# full_computer.net
KiCad netlist of a schematic drawn in EAGLE
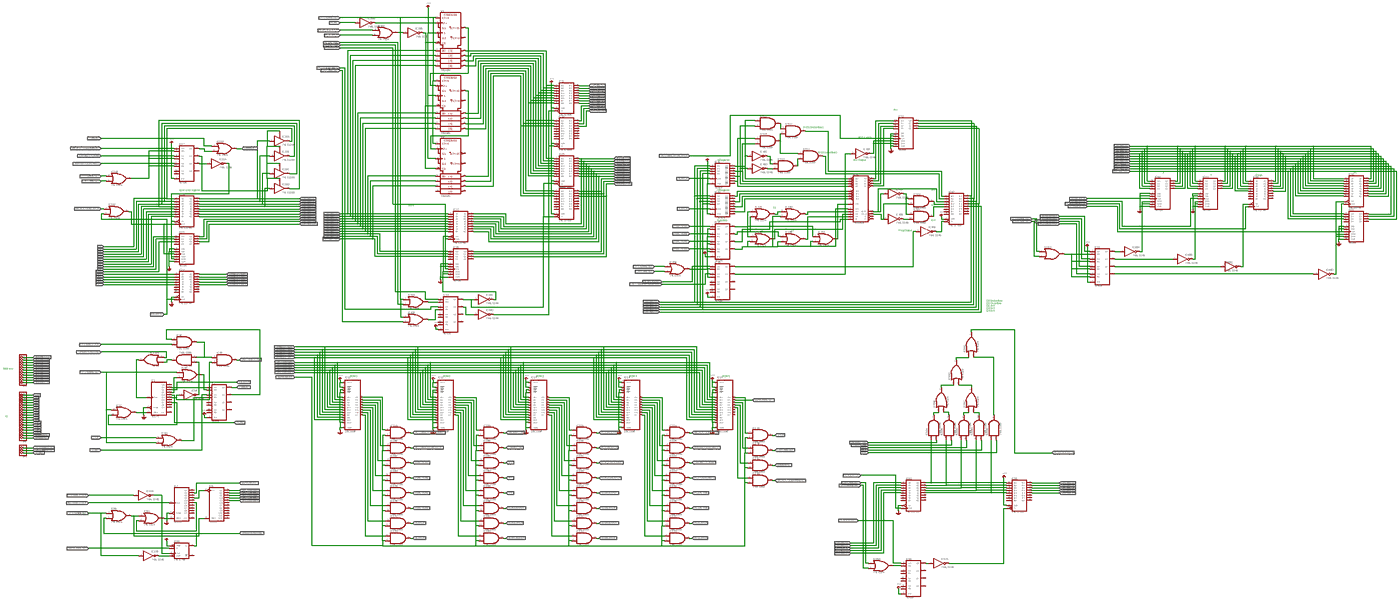
[diagram p0: schematic, sheet 1, overview]
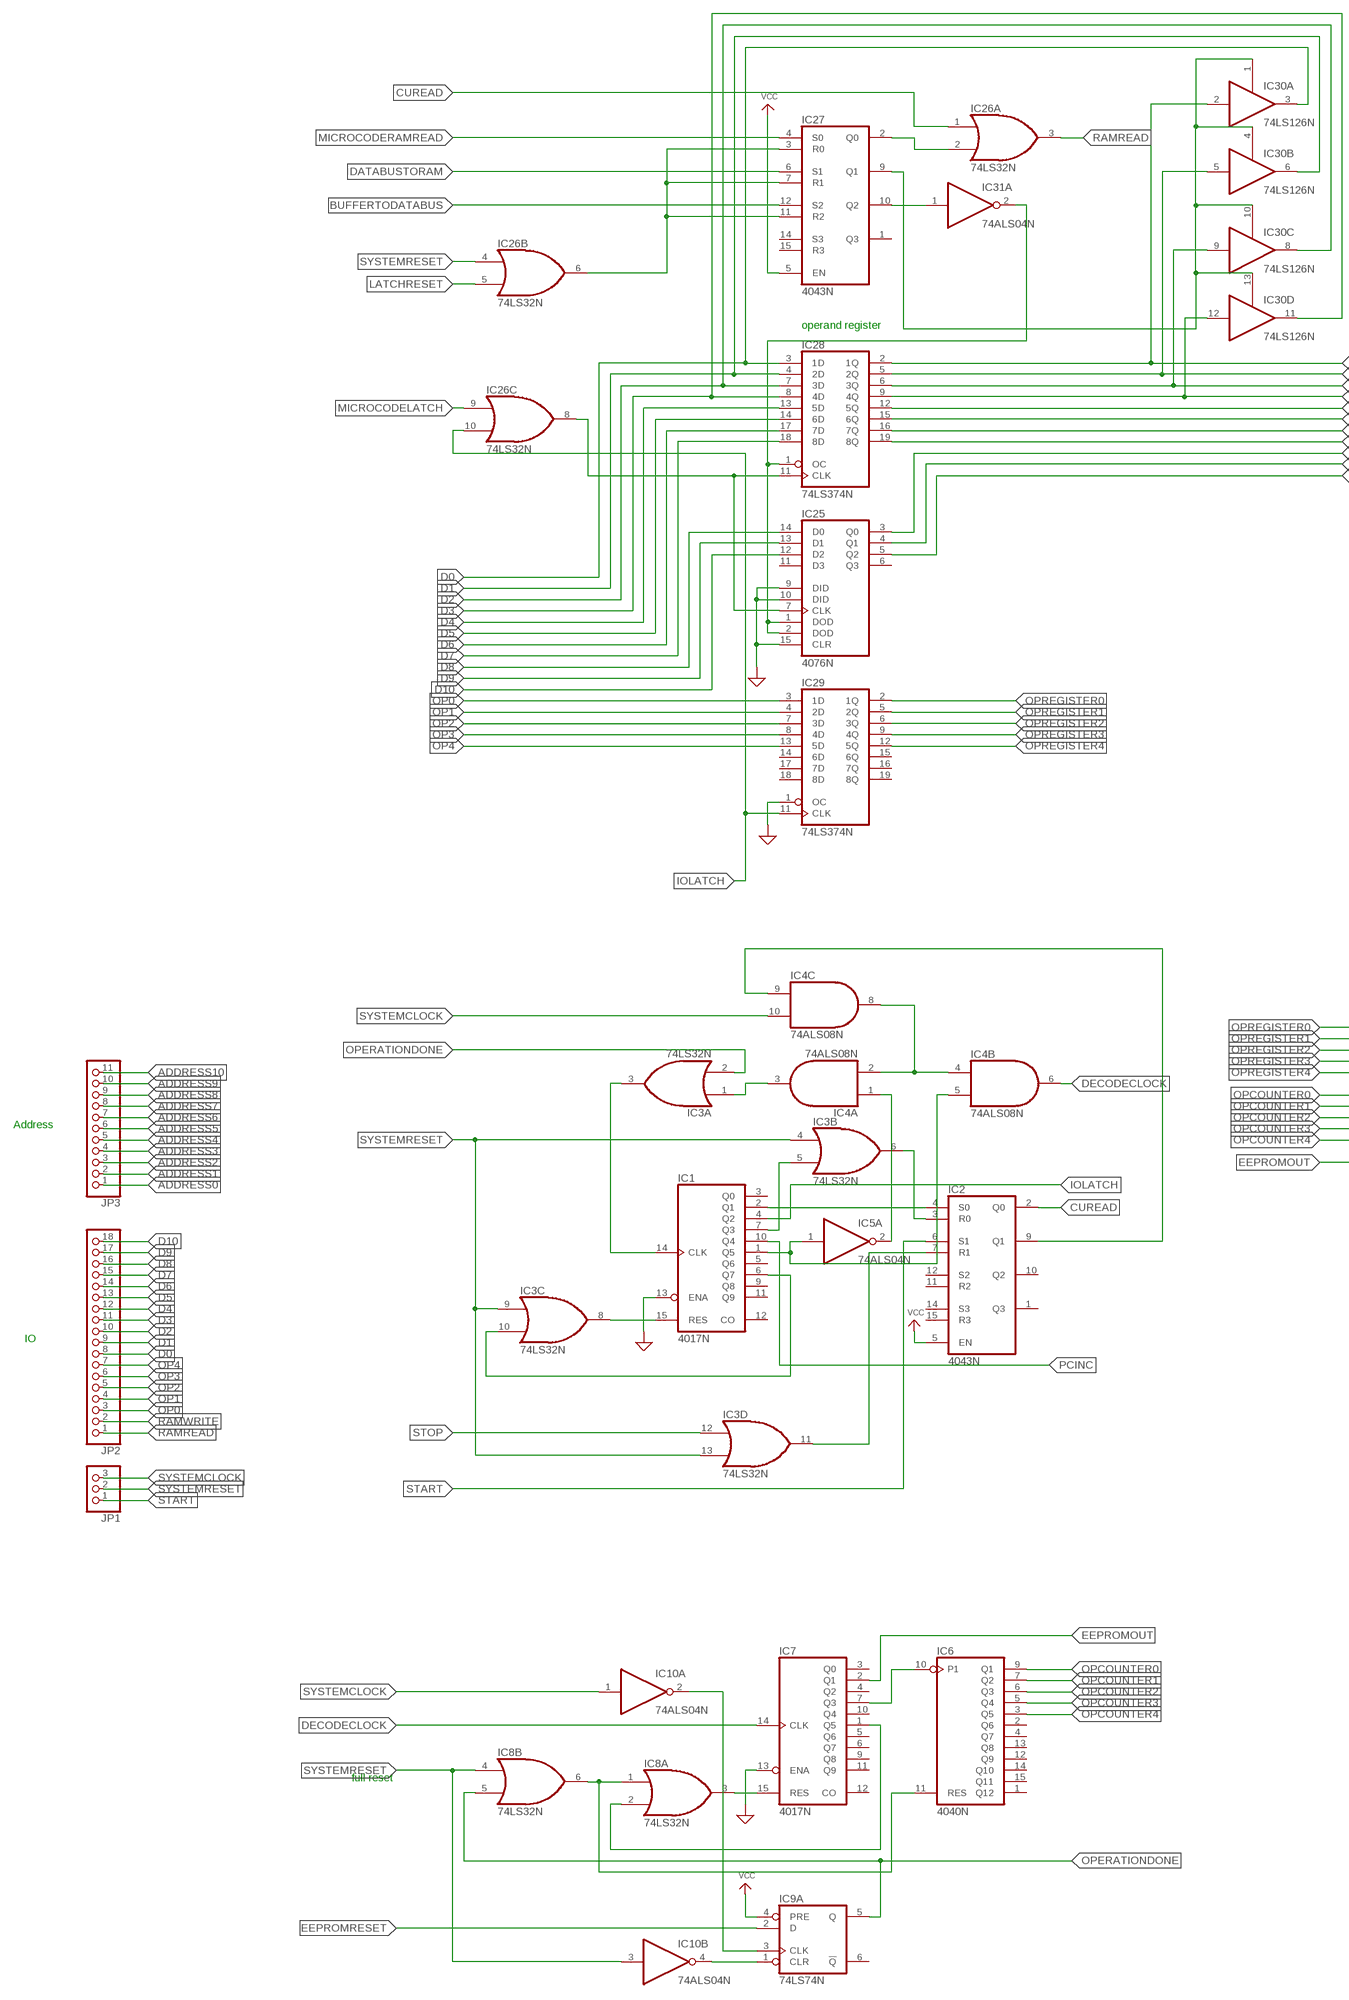
[diagram p1: schematic, sheet 1, part 1 of 6]
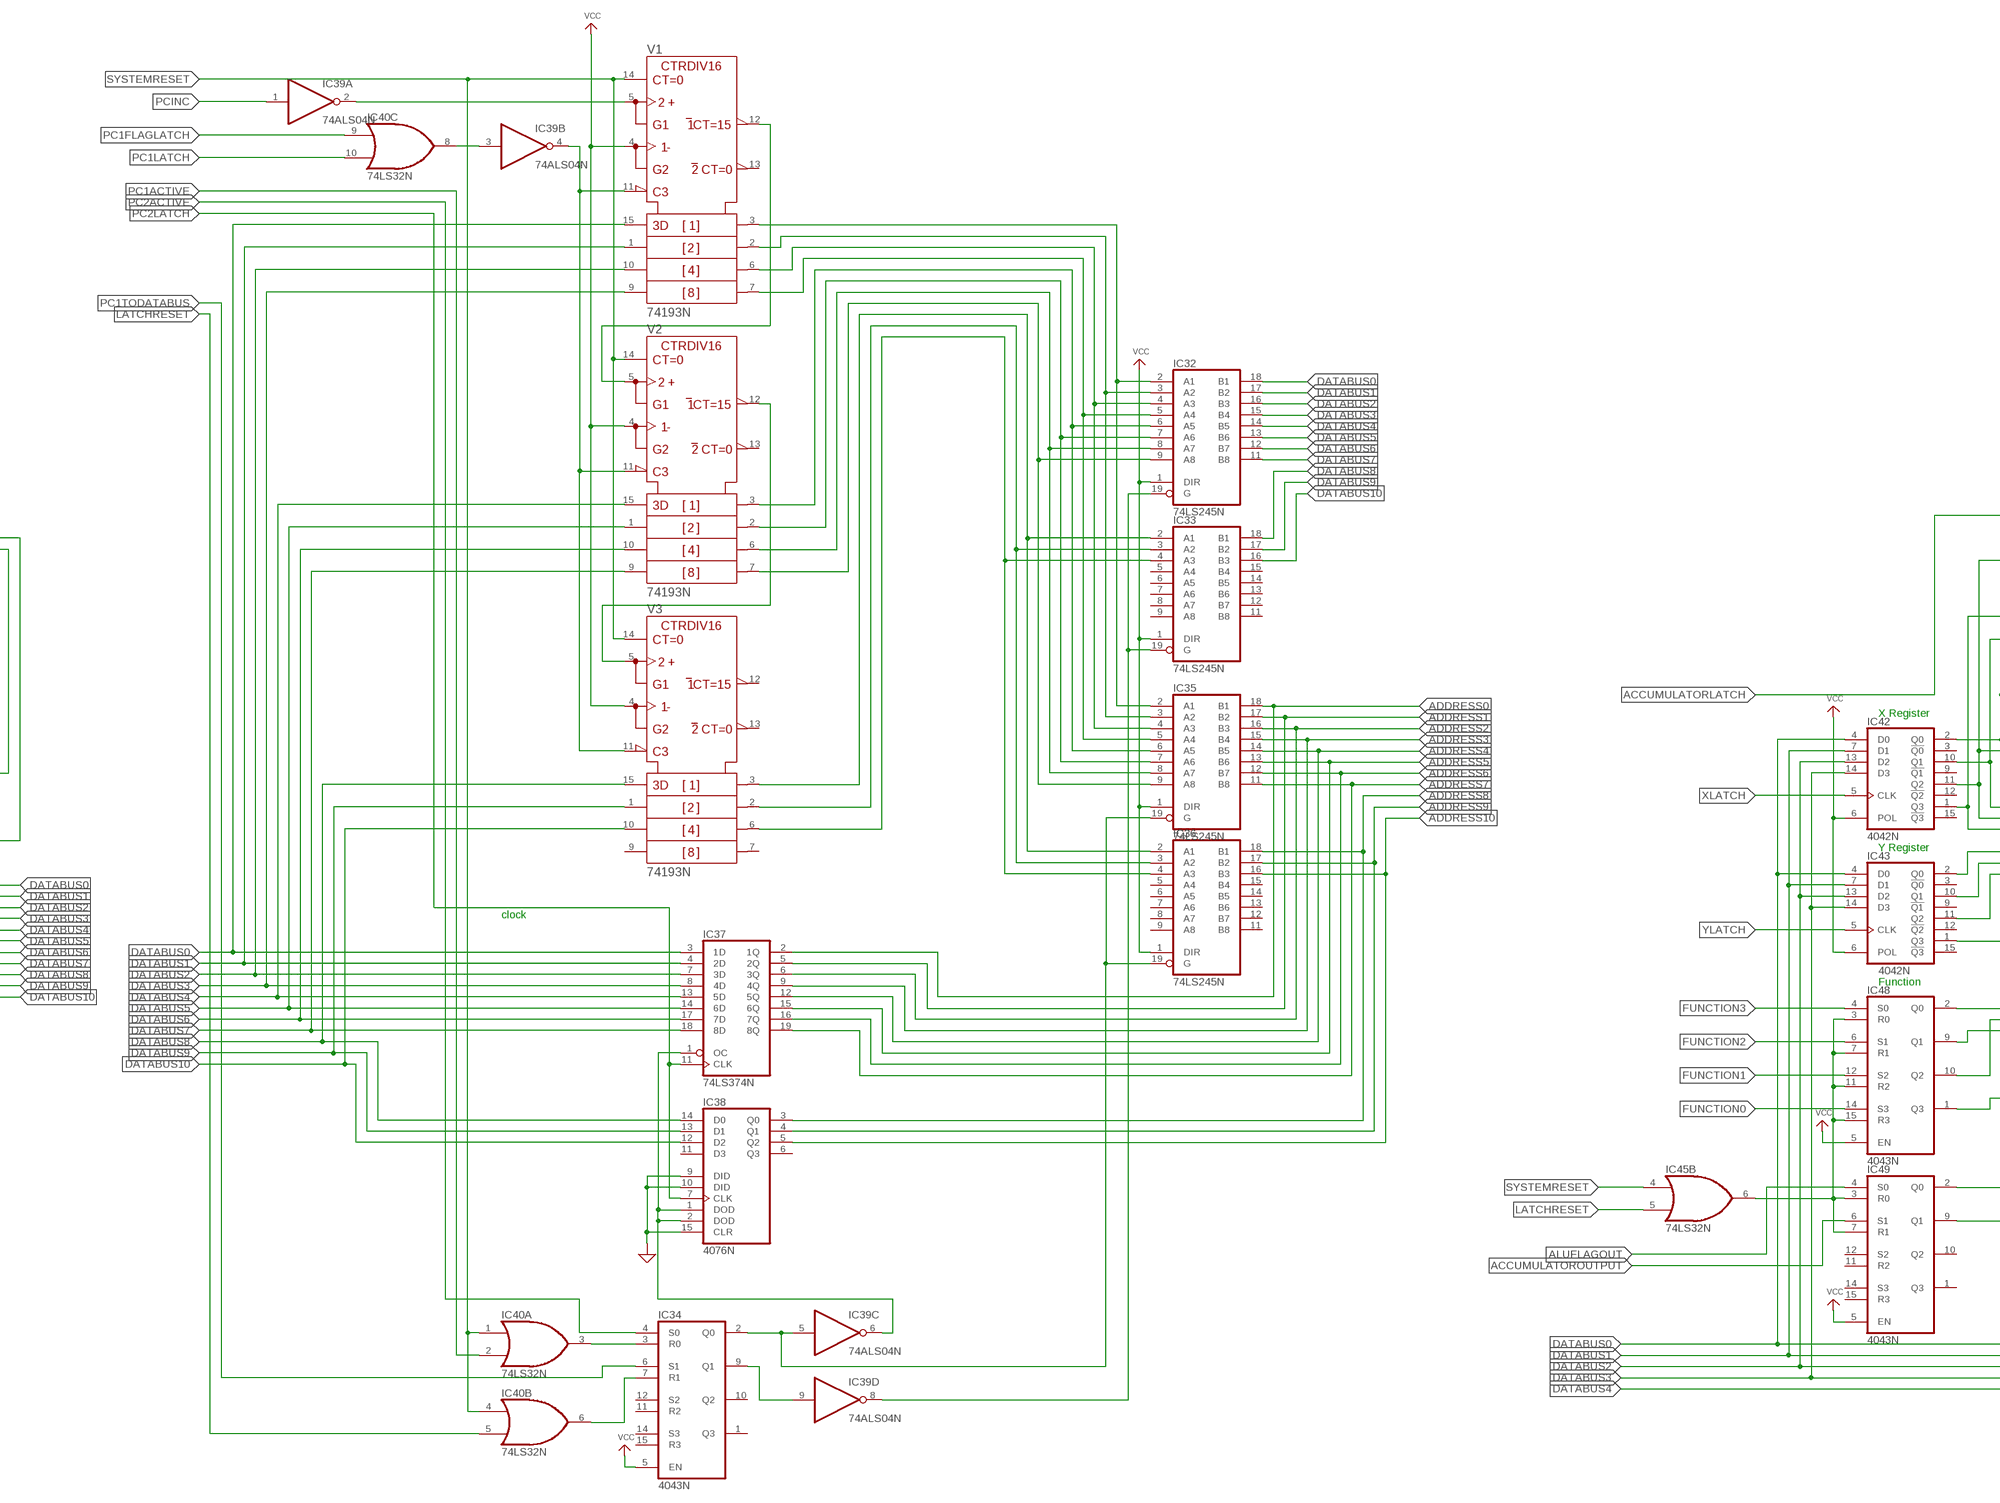
[diagram p2: schematic, sheet 1, part 2 of 6]
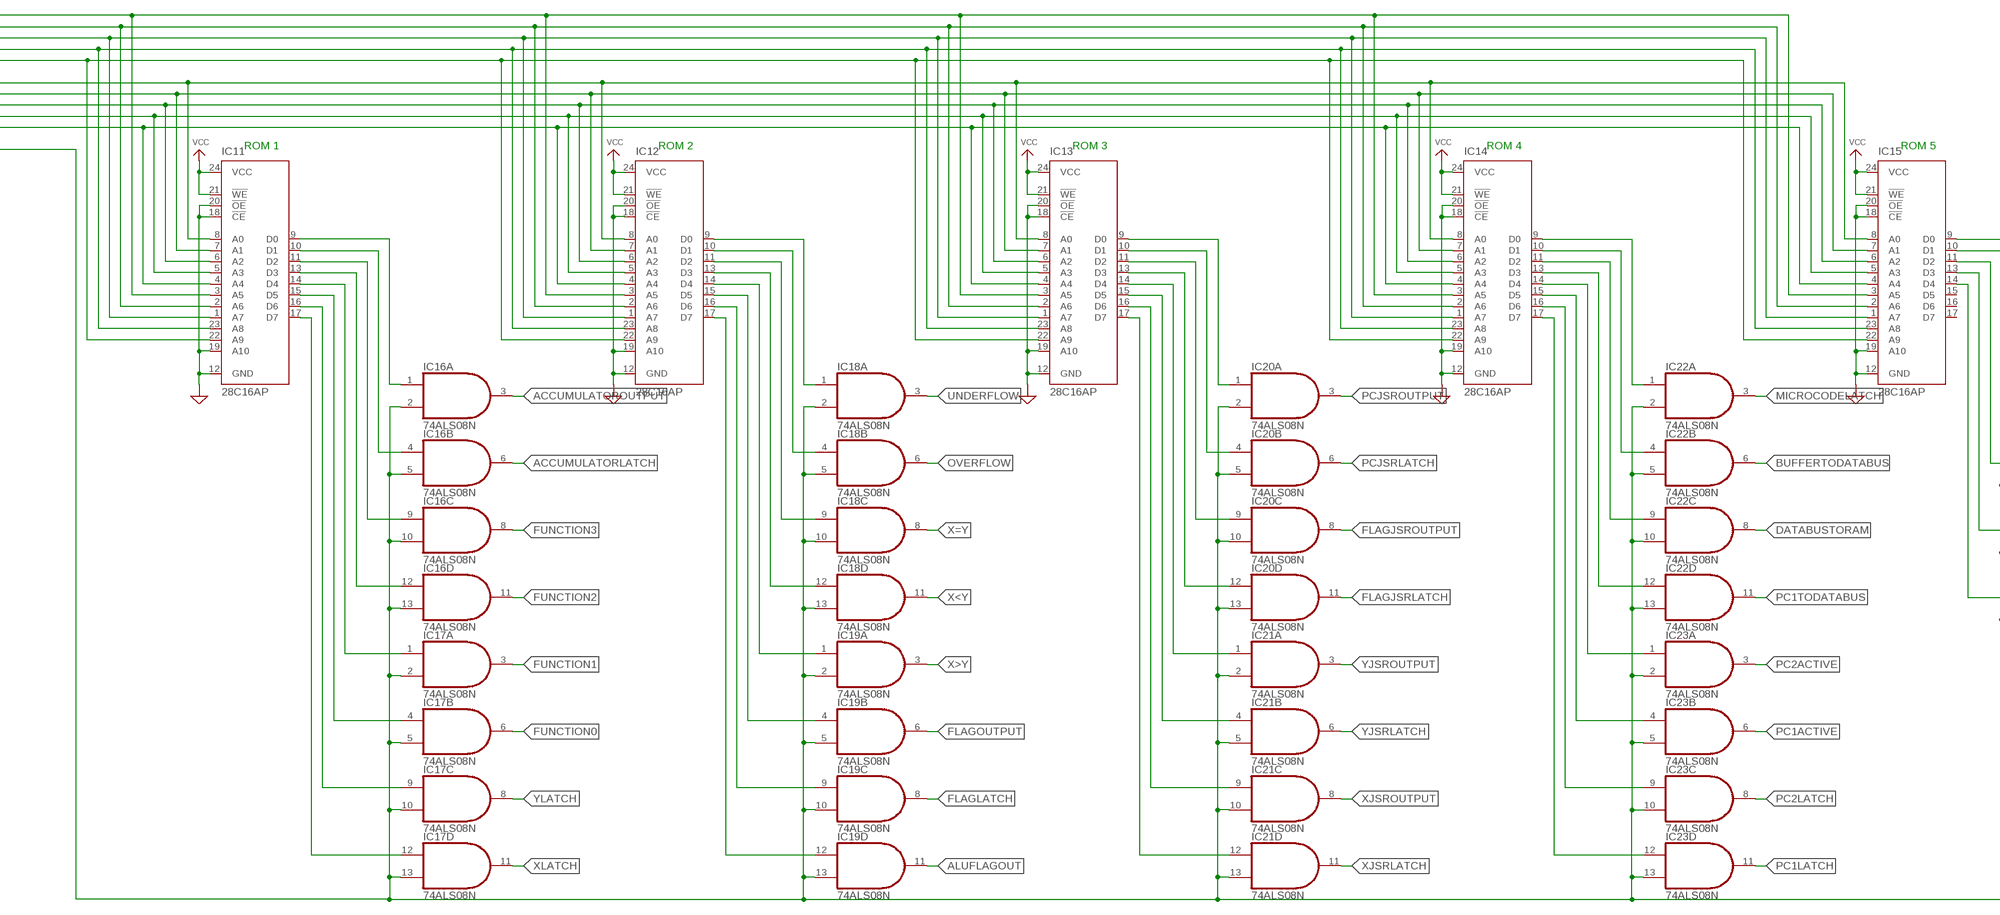
[diagram p3: schematic, sheet 1, part 3 of 6]
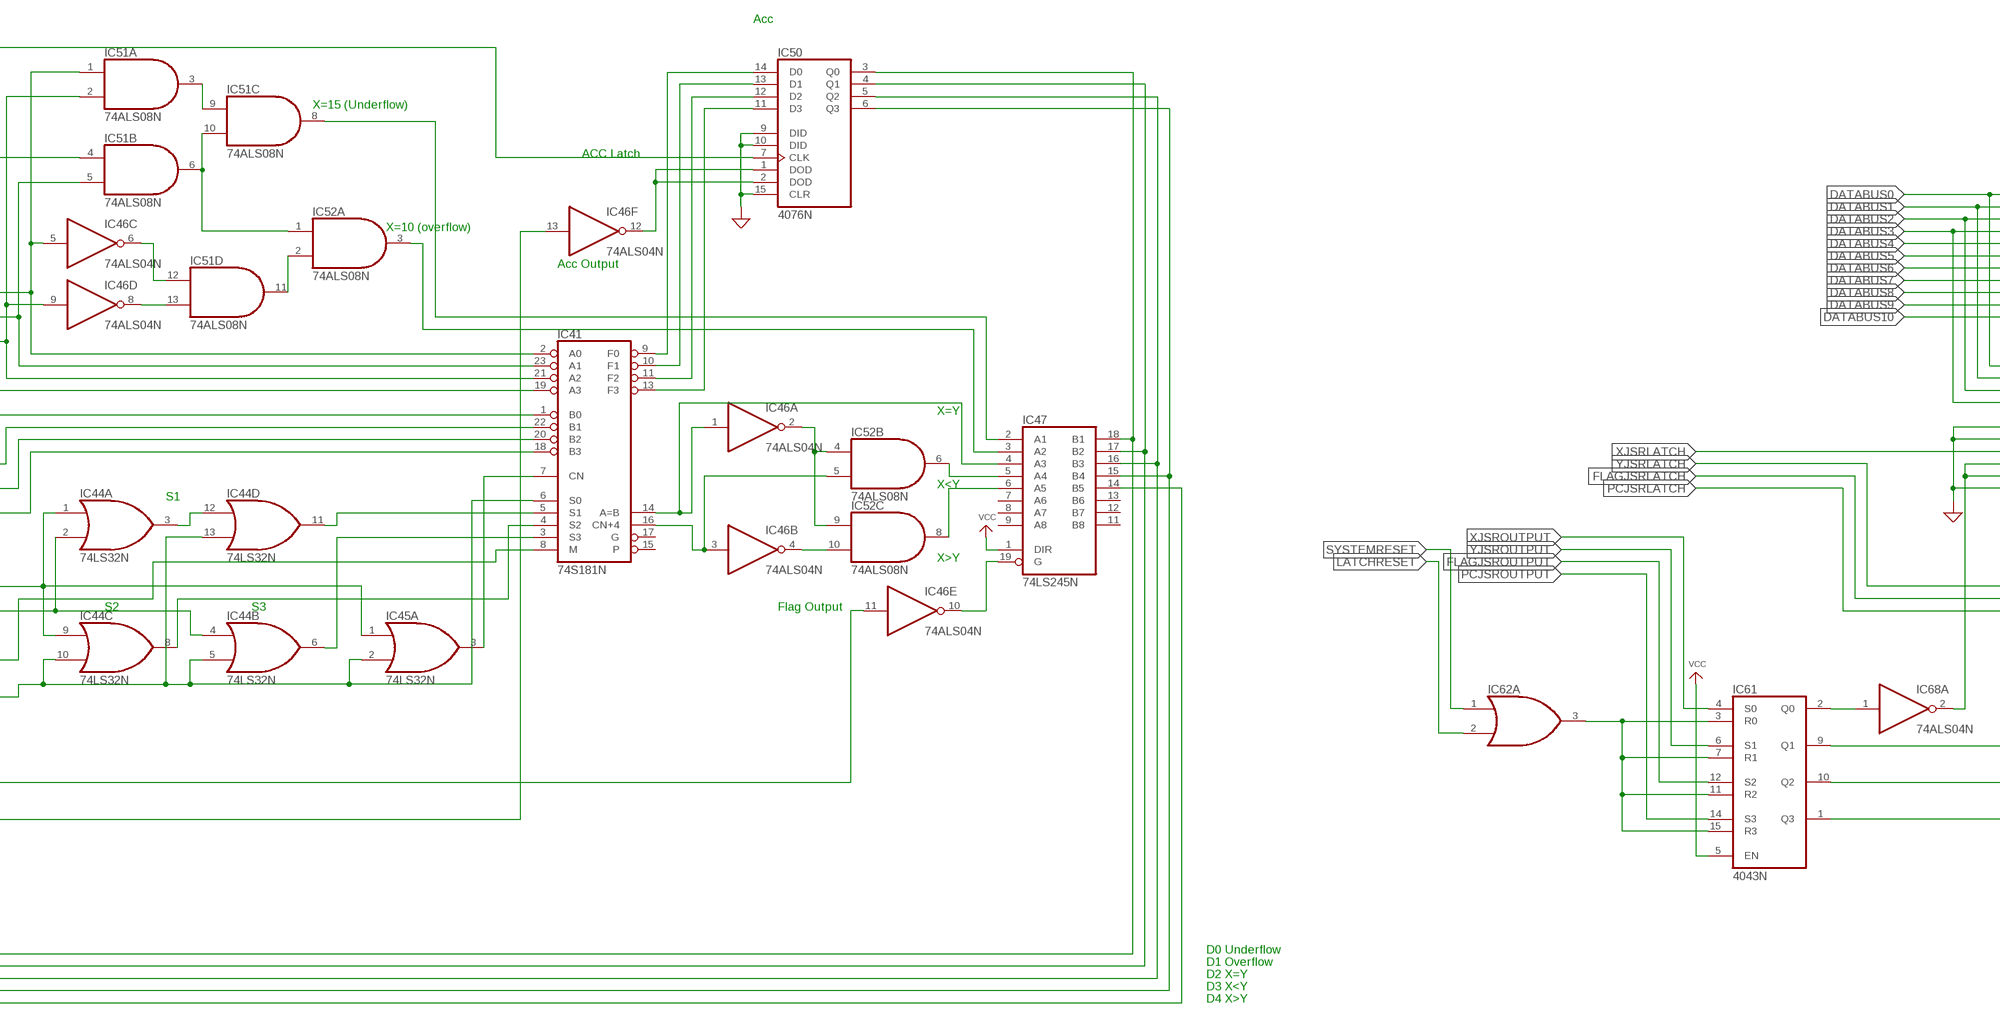
[diagram p4: schematic, sheet 1, part 4 of 6]
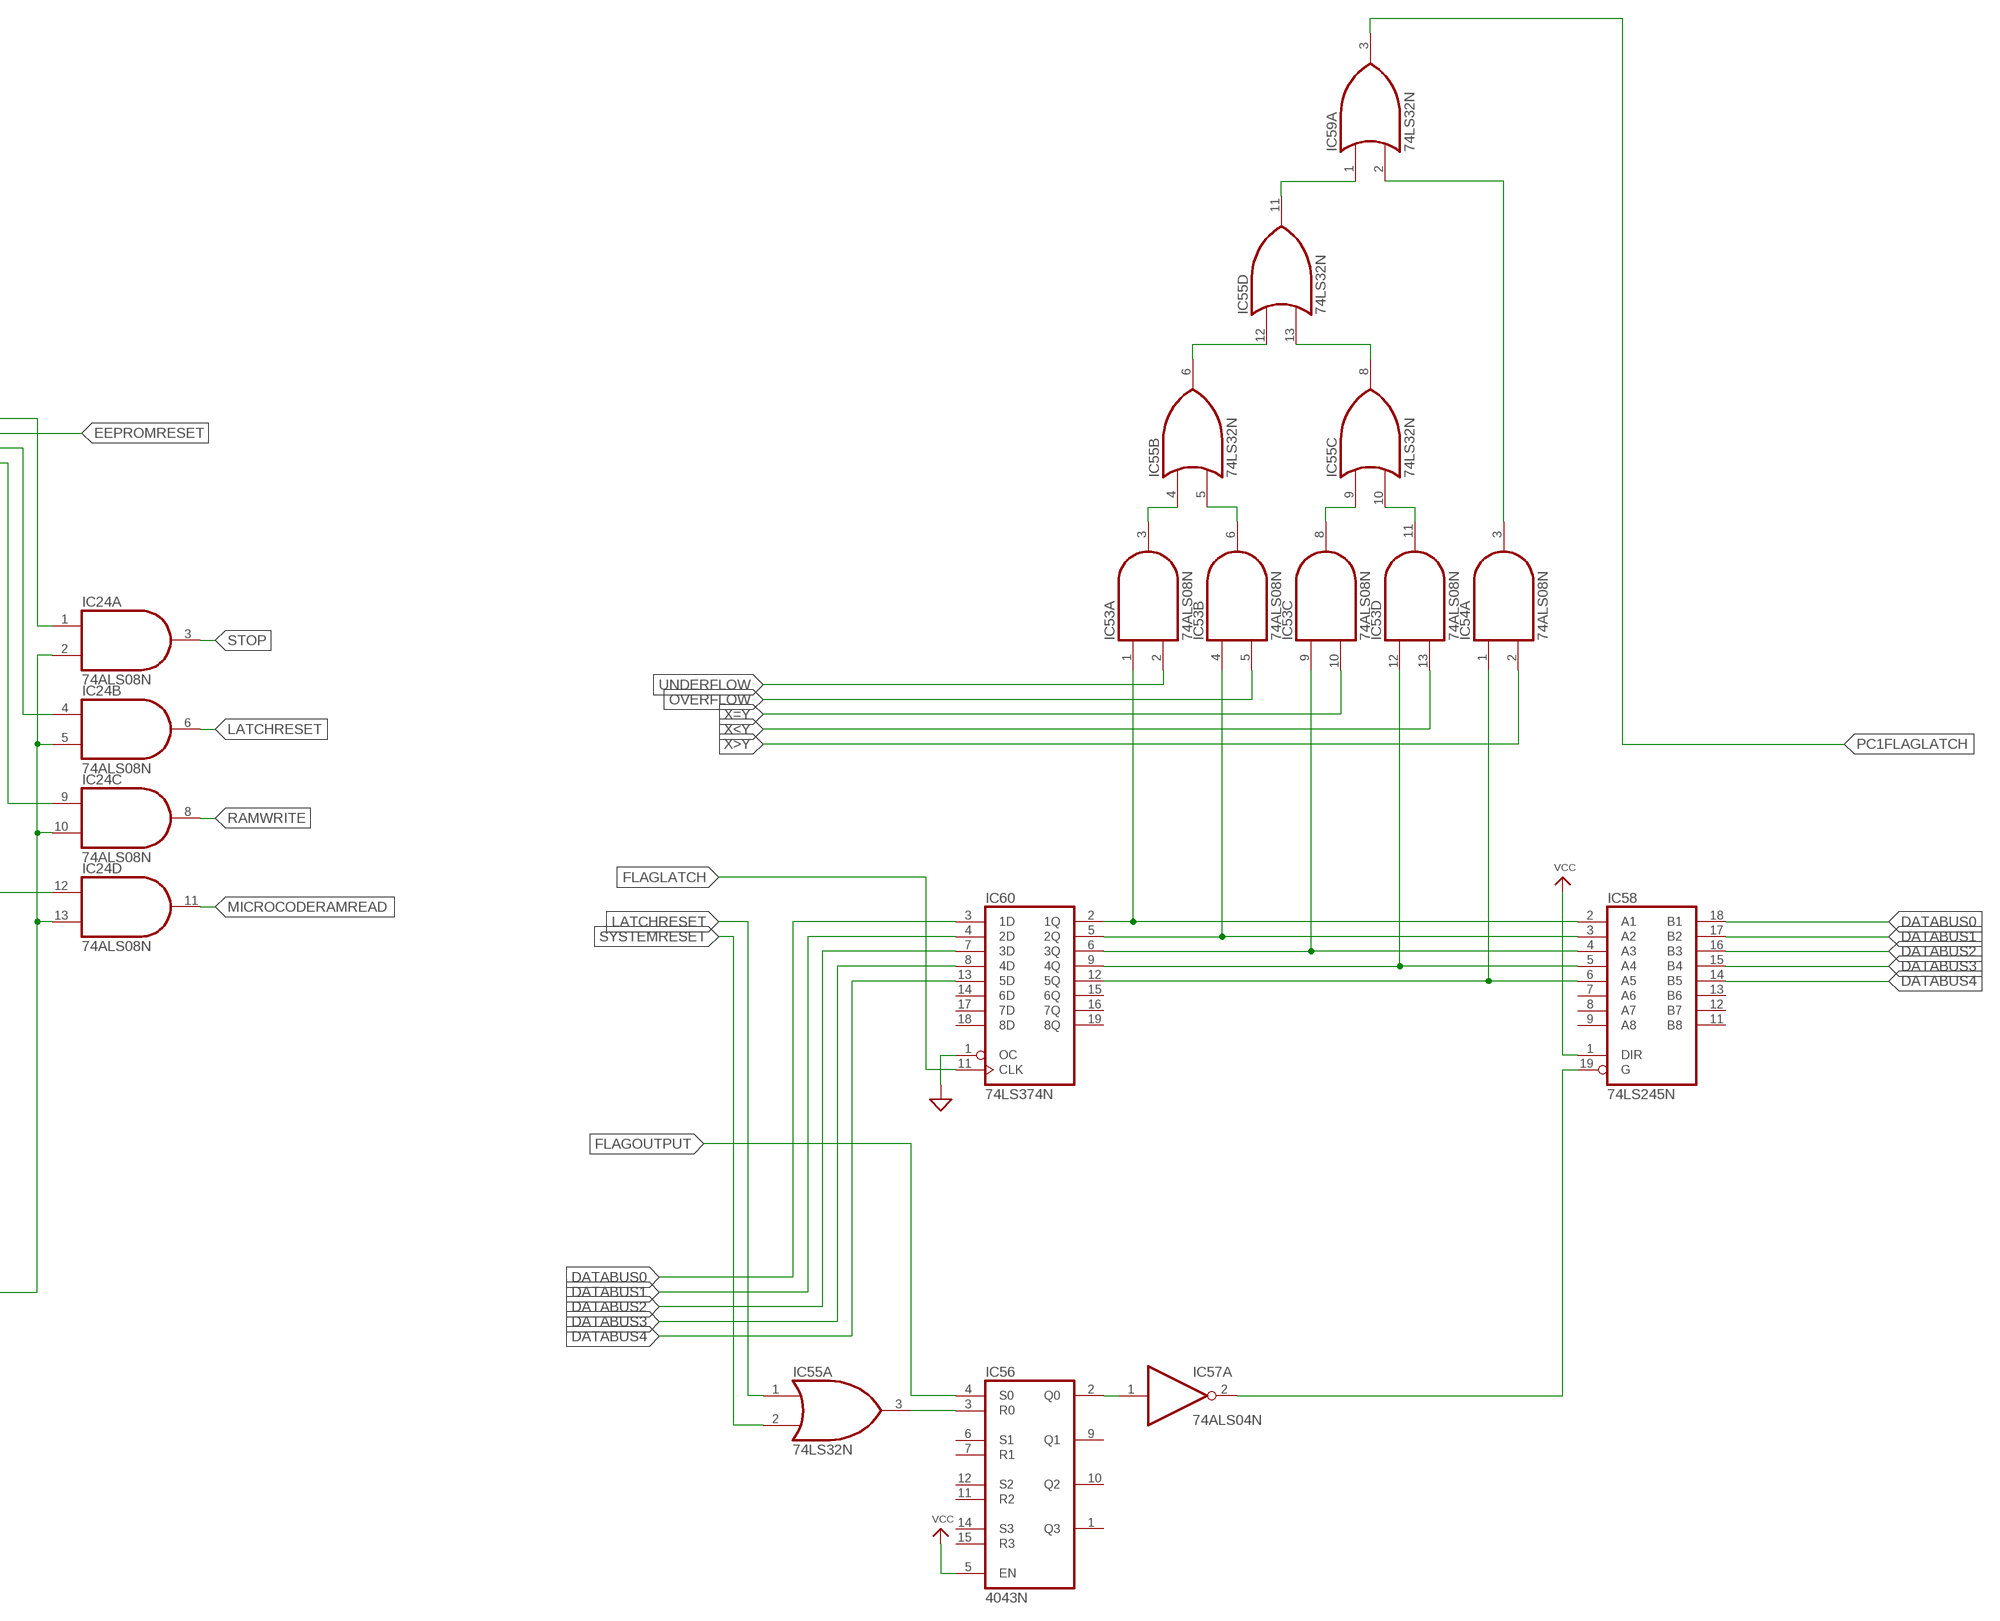
[diagram p5: schematic, sheet 1, part 5 of 6]
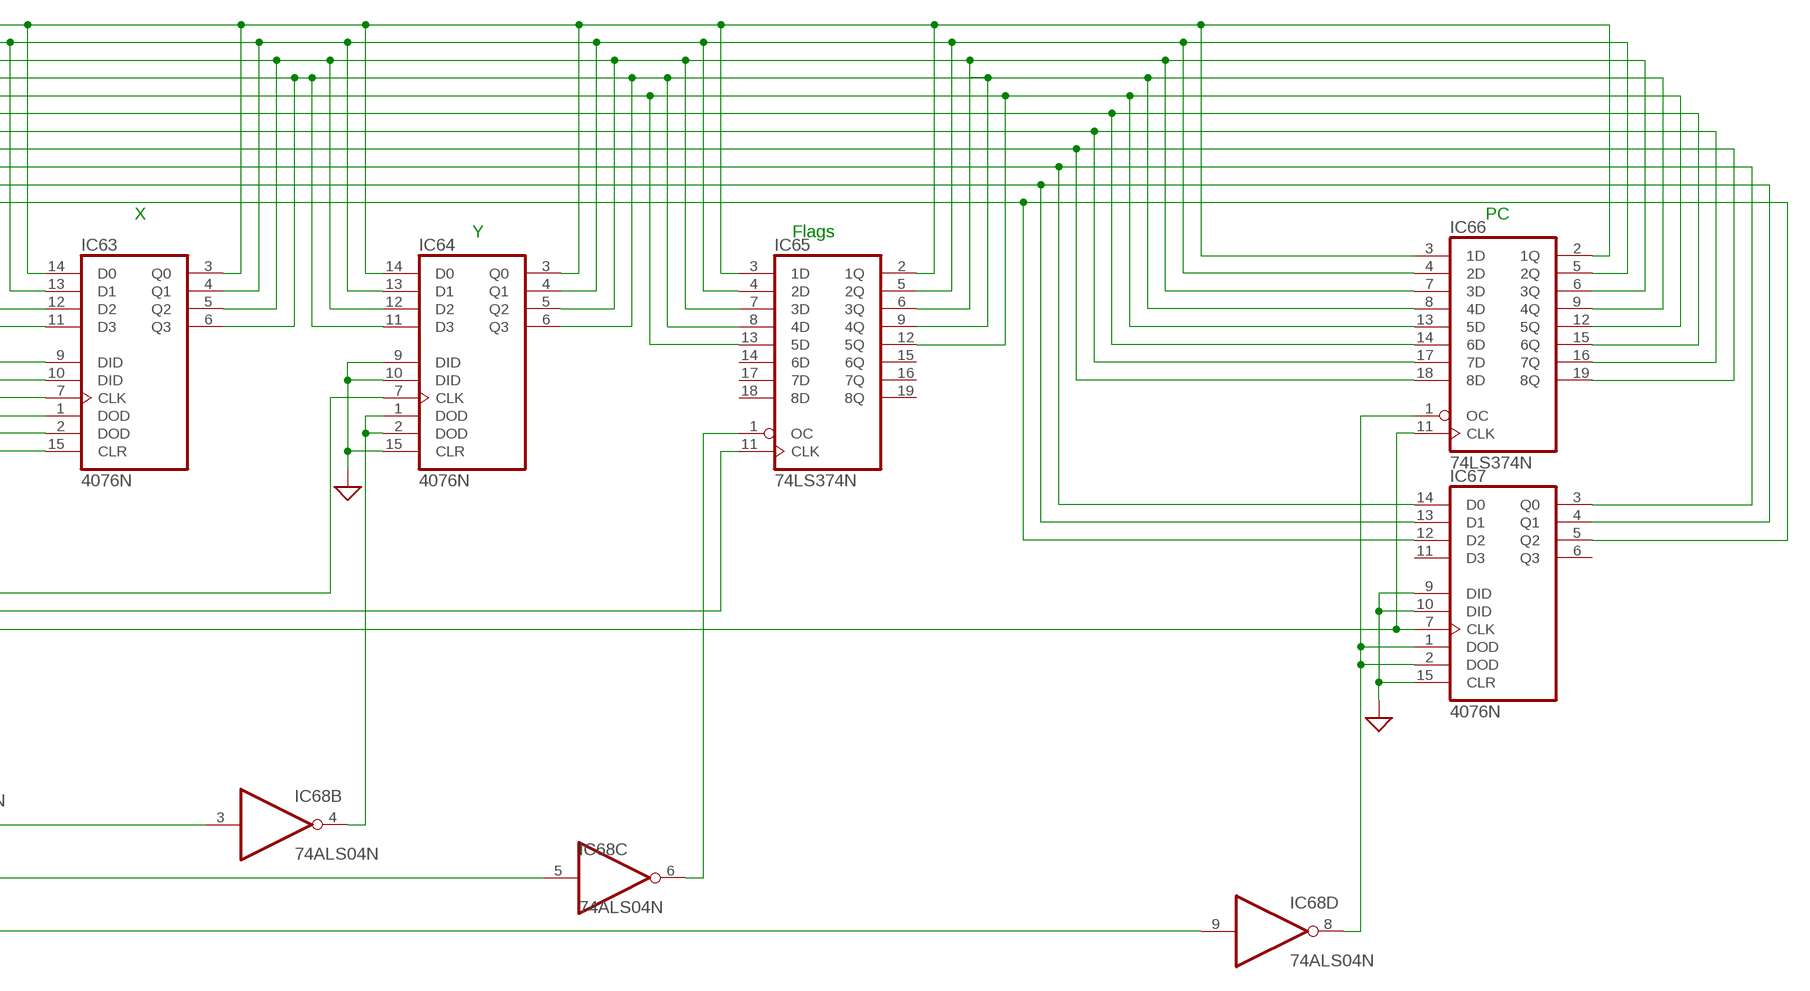
[diagram p6: schematic, sheet 1, part 6 of 6]

(export (version "E")
  (design (tool "Eeschema 10.0.6"))
  (components
    (comp (ref "IC1")
      (value "4017N")
      (footprint "eagle-import:DIL16")
      (libsource (lib "eagle-import") (part "4017N"))
    )
    (comp (ref "IC2")
      (value "4043N")
      (footprint "eagle-import:DIL16")
      (libsource (lib "eagle-import") (part "4043N"))
    )
    (comp (ref "IC3")
      (value "74LS32N")
      (footprint "eagle-import:DIL14")
      (libsource (lib "eagle-import") (part "7432NLS"))
    )
    (comp (ref "IC4")
      (value "74ALS08N")
      (footprint "eagle-import:DIL14")
      (libsource (lib "eagle-import") (part "7408NALS"))
    )
    (comp (ref "IC5")
      (value "74ALS04N")
      (footprint "eagle-import:DIL14")
      (libsource (lib "eagle-import") (part "7404NALS"))
    )
    (comp (ref "IC6")
      (value "4040N")
      (footprint "eagle-import:DIL16")
      (libsource (lib "eagle-import") (part "4040N"))
    )
    (comp (ref "IC7")
      (value "4017N")
      (footprint "eagle-import:DIL16")
      (libsource (lib "eagle-import") (part "4017N"))
    )
    (comp (ref "IC8")
      (value "74LS32N")
      (footprint "eagle-import:DIL14")
      (libsource (lib "eagle-import") (part "7432NLS"))
    )
    (comp (ref "IC9")
      (value "74LS74N")
      (footprint "eagle-import:DIL14")
      (libsource (lib "eagle-import") (part "7474NLS"))
    )
    (comp (ref "IC10")
      (value "74ALS04N")
      (footprint "eagle-import:DIL14")
      (libsource (lib "eagle-import") (part "7404NALS"))
    )
    (comp (ref "IC11")
      (value "28C16AP")
      (footprint "eagle-import:DIL24-6")
      (fields (field (name "MPN") "CAT28C16ALI-12"))
      (libsource (lib "eagle-import") (part "2816APC"))
    )
    (comp (ref "IC12")
      (value "28C16AP")
      (footprint "eagle-import:DIL24-6")
      (fields (field (name "MPN") "CAT28C16ALI-12"))
      (libsource (lib "eagle-import") (part "2816APC"))
    )
    (comp (ref "IC13")
      (value "28C16AP")
      (footprint "eagle-import:DIL24-6")
      (fields (field (name "MPN") "CAT28C16ALI-12"))
      (libsource (lib "eagle-import") (part "2816APC"))
    )
    (comp (ref "IC14")
      (value "28C16AP")
      (footprint "eagle-import:DIL24-6")
      (fields (field (name "MPN") "CAT28C16ALI-12"))
      (libsource (lib "eagle-import") (part "2816APC"))
    )
    (comp (ref "IC15")
      (value "28C16AP")
      (footprint "eagle-import:DIL24-6")
      (fields (field (name "MPN") "CAT28C16ALI-12"))
      (libsource (lib "eagle-import") (part "2816APC"))
    )
    (comp (ref "IC16")
      (value "74ALS08N")
      (footprint "eagle-import:DIL14")
      (libsource (lib "eagle-import") (part "7408NALS"))
    )
    (comp (ref "IC17")
      (value "74ALS08N")
      (footprint "eagle-import:DIL14")
      (libsource (lib "eagle-import") (part "7408NALS"))
    )
    (comp (ref "IC18")
      (value "74ALS08N")
      (footprint "eagle-import:DIL14")
      (libsource (lib "eagle-import") (part "7408NALS"))
    )
    (comp (ref "IC19")
      (value "74ALS08N")
      (footprint "eagle-import:DIL14")
      (libsource (lib "eagle-import") (part "7408NALS"))
    )
    (comp (ref "IC20")
      (value "74ALS08N")
      (footprint "eagle-import:DIL14")
      (libsource (lib "eagle-import") (part "7408NALS"))
    )
    (comp (ref "IC21")
      (value "74ALS08N")
      (footprint "eagle-import:DIL14")
      (libsource (lib "eagle-import") (part "7408NALS"))
    )
    (comp (ref "IC22")
      (value "74ALS08N")
      (footprint "eagle-import:DIL14")
      (libsource (lib "eagle-import") (part "7408NALS"))
    )
    (comp (ref "IC23")
      (value "74ALS08N")
      (footprint "eagle-import:DIL14")
      (libsource (lib "eagle-import") (part "7408NALS"))
    )
    (comp (ref "IC24")
      (value "74ALS08N")
      (footprint "eagle-import:DIL14")
      (libsource (lib "eagle-import") (part "7408NALS"))
    )
    (comp (ref "IC25")
      (value "4076N")
      (footprint "eagle-import:DIL16")
      (libsource (lib "eagle-import") (part "4076N"))
    )
    (comp (ref "IC26")
      (value "74LS32N")
      (footprint "eagle-import:DIL14")
      (libsource (lib "eagle-import") (part "7432NLS"))
    )
    (comp (ref "IC27")
      (value "4043N")
      (footprint "eagle-import:DIL16")
      (libsource (lib "eagle-import") (part "4043N"))
    )
    (comp (ref "IC28")
      (value "74LS374N")
      (footprint "eagle-import:DIL20")
      (libsource (lib "eagle-import") (part "74374NLS"))
    )
    (comp (ref "IC29")
      (value "74LS374N")
      (footprint "eagle-import:DIL20")
      (libsource (lib "eagle-import") (part "74374NLS"))
    )
    (comp (ref "IC30")
      (value "74LS126N")
      (footprint "eagle-import:DIL14")
      (libsource (lib "eagle-import") (part "74126NLS"))
    )
    (comp (ref "IC31")
      (value "74ALS04N")
      (footprint "eagle-import:DIL14")
      (libsource (lib "eagle-import") (part "7404NALS"))
    )
    (comp (ref "IC32")
      (value "74LS245N")
      (footprint "eagle-import:DIL20")
      (libsource (lib "eagle-import") (part "74245NLS"))
    )
    (comp (ref "IC33")
      (value "74LS245N")
      (footprint "eagle-import:DIL20")
      (libsource (lib "eagle-import") (part "74245NLS"))
    )
    (comp (ref "IC34")
      (value "4043N")
      (footprint "eagle-import:DIL16")
      (libsource (lib "eagle-import") (part "4043N"))
    )
    (comp (ref "IC35")
      (value "74LS245N")
      (footprint "eagle-import:DIL20")
      (libsource (lib "eagle-import") (part "74245NLS"))
    )
    (comp (ref "IC36")
      (value "74LS245N")
      (footprint "eagle-import:DIL20")
      (libsource (lib "eagle-import") (part "74245NLS"))
    )
    (comp (ref "IC37")
      (value "74LS374N")
      (footprint "eagle-import:DIL20")
      (libsource (lib "eagle-import") (part "74374NLS"))
    )
    (comp (ref "IC38")
      (value "4076N")
      (footprint "eagle-import:DIL16")
      (libsource (lib "eagle-import") (part "4076N"))
    )
    (comp (ref "IC39")
      (value "74ALS04N")
      (footprint "eagle-import:DIL14")
      (libsource (lib "eagle-import") (part "7404NALS"))
    )
    (comp (ref "IC40")
      (value "74LS32N")
      (footprint "eagle-import:DIL14")
      (libsource (lib "eagle-import") (part "7432NLS"))
    )
    (comp (ref "IC41")
      (value "74S181N")
      (footprint "eagle-import:DIL24-6")
      (libsource (lib "eagle-import") (part "74181NS"))
    )
    (comp (ref "IC42")
      (value "4042N")
      (footprint "eagle-import:DIL16")
      (libsource (lib "eagle-import") (part "4042N"))
    )
    (comp (ref "IC43")
      (value "4042N")
      (footprint "eagle-import:DIL16")
      (libsource (lib "eagle-import") (part "4042N"))
    )
    (comp (ref "IC44")
      (value "74LS32N")
      (footprint "eagle-import:DIL14")
      (libsource (lib "eagle-import") (part "7432NLS"))
    )
    (comp (ref "IC45")
      (value "74LS32N")
      (footprint "eagle-import:DIL14")
      (libsource (lib "eagle-import") (part "7432NLS"))
    )
    (comp (ref "IC46")
      (value "74ALS04N")
      (footprint "eagle-import:DIL14")
      (libsource (lib "eagle-import") (part "7404NALS"))
    )
    (comp (ref "IC47")
      (value "74LS245N")
      (footprint "eagle-import:DIL20")
      (libsource (lib "eagle-import") (part "74245NLS"))
    )
    (comp (ref "IC48")
      (value "4043N")
      (footprint "eagle-import:DIL16")
      (libsource (lib "eagle-import") (part "4043N"))
    )
    (comp (ref "IC49")
      (value "4043N")
      (footprint "eagle-import:DIL16")
      (libsource (lib "eagle-import") (part "4043N"))
    )
    (comp (ref "IC50")
      (value "4076N")
      (footprint "eagle-import:DIL16")
      (libsource (lib "eagle-import") (part "4076N"))
    )
    (comp (ref "IC51")
      (value "74ALS08N")
      (footprint "eagle-import:DIL14")
      (libsource (lib "eagle-import") (part "7408NALS"))
    )
    (comp (ref "IC52")
      (value "74ALS08N")
      (footprint "eagle-import:DIL14")
      (libsource (lib "eagle-import") (part "7408NALS"))
    )
    (comp (ref "IC53")
      (value "74ALS08N")
      (footprint "eagle-import:DIL14")
      (libsource (lib "eagle-import") (part "7408NALS"))
    )
    (comp (ref "IC54")
      (value "74ALS08N")
      (footprint "eagle-import:DIL14")
      (libsource (lib "eagle-import") (part "7408NALS"))
    )
    (comp (ref "IC55")
      (value "74LS32N")
      (footprint "eagle-import:DIL14")
      (libsource (lib "eagle-import") (part "7432NLS"))
    )
    (comp (ref "IC56")
      (value "4043N")
      (footprint "eagle-import:DIL16")
      (libsource (lib "eagle-import") (part "4043N"))
    )
    (comp (ref "IC57")
      (value "74ALS04N")
      (footprint "eagle-import:DIL14")
      (libsource (lib "eagle-import") (part "7404NALS"))
    )
    (comp (ref "IC58")
      (value "74LS245N")
      (footprint "eagle-import:DIL20")
      (libsource (lib "eagle-import") (part "74245NLS"))
    )
    (comp (ref "IC59")
      (value "74LS32N")
      (footprint "eagle-import:DIL14")
      (libsource (lib "eagle-import") (part "7432NLS"))
    )
    (comp (ref "IC60")
      (value "74LS374N")
      (footprint "eagle-import:DIL20")
      (libsource (lib "eagle-import") (part "74374NLS"))
    )
    (comp (ref "IC61")
      (value "4043N")
      (footprint "eagle-import:DIL16")
      (libsource (lib "eagle-import") (part "4043N"))
    )
    (comp (ref "IC62")
      (value "74LS32N")
      (footprint "eagle-import:DIL14")
      (libsource (lib "eagle-import") (part "7432NLS"))
    )
    (comp (ref "IC63")
      (value "4076N")
      (footprint "eagle-import:DIL16")
      (libsource (lib "eagle-import") (part "4076N"))
    )
    (comp (ref "IC64")
      (value "4076N")
      (footprint "eagle-import:DIL16")
      (libsource (lib "eagle-import") (part "4076N"))
    )
    (comp (ref "IC65")
      (value "74LS374N")
      (footprint "eagle-import:DIL20")
      (libsource (lib "eagle-import") (part "74374NLS"))
    )
    (comp (ref "IC66")
      (value "74LS374N")
      (footprint "eagle-import:DIL20")
      (libsource (lib "eagle-import") (part "74374NLS"))
    )
    (comp (ref "IC67")
      (value "4076N")
      (footprint "eagle-import:DIL16")
      (libsource (lib "eagle-import") (part "4076N"))
    )
    (comp (ref "IC68")
      (value "74ALS04N")
      (footprint "eagle-import:DIL14")
      (libsource (lib "eagle-import") (part "7404NALS"))
    )
    (comp (ref "JP1")
      (value "PINHD-1X3")
      (footprint "eagle-import:1X03")
      (libsource (lib "eagle-import") (part "PINHD-1X3"))
    )
    (comp (ref "JP2")
      (value "PINHD-1X18")
      (footprint "eagle-import:1X18")
      (libsource (lib "eagle-import") (part "PINHD-1X18"))
    )
    (comp (ref "JP3")
      (value "PINHD-1X11")
      (footprint "eagle-import:1X11")
      (libsource (lib "eagle-import") (part "PINHD-1X11"))
    )
    (comp (ref "V1")
      (value "74193N")
      (footprint "eagle-import:DIL16")
      (libsource (lib "eagle-import") (part "74193N"))
    )
    (comp (ref "V2")
      (value "74193N")
      (footprint "eagle-import:DIL16")
      (libsource (lib "eagle-import") (part "74193N"))
    )
    (comp (ref "V3")
      (value "74193N")
      (footprint "eagle-import:DIL16")
      (libsource (lib "eagle-import") (part "74193N"))
    )
  )
  (nets
    (net (code "1") (name "ACCUMULATORLATCH") (class "Default")
      (node (ref "IC16") (pin "6") (pinfunction "O_6") (pintype "output"))
      (node (ref "IC50") (pin "7") (pinfunction "CLK_7") (pintype "input"))
    )
    (net (code "2") (name "ACCUMULATOROUTPUT") (class "Default")
      (node (ref "IC16") (pin "3") (pinfunction "O_3") (pintype "output"))
      (node (ref "IC49") (pin "6") (pinfunction "S1_6") (pintype "input"))
    )
    (net (code "3") (name "ADDRESS0") (class "Default")
      (node (ref "IC35") (pin "18") (pinfunction "B1_18") (pintype "bidirectional"))
      (node (ref "IC37") (pin "2") (pinfunction "1Q_2") (pintype "tri_state"))
      (node (ref "JP3") (pin "1") (pinfunction "1_1") (pintype "passive"))
    )
    (net (code "4") (name "ADDRESS1") (class "Default")
      (node (ref "IC35") (pin "17") (pinfunction "B2_17") (pintype "bidirectional"))
      (node (ref "IC37") (pin "5") (pinfunction "2Q_5") (pintype "tri_state"))
      (node (ref "JP3") (pin "2") (pinfunction "2_2") (pintype "passive"))
    )
    (net (code "5") (name "ADDRESS2") (class "Default")
      (node (ref "IC35") (pin "16") (pinfunction "B3_16") (pintype "bidirectional"))
      (node (ref "IC37") (pin "6") (pinfunction "3Q_6") (pintype "tri_state"))
      (node (ref "JP3") (pin "3") (pinfunction "3_3") (pintype "passive"))
    )
    (net (code "6") (name "ADDRESS3") (class "Default")
      (node (ref "IC35") (pin "15") (pinfunction "B4_15") (pintype "bidirectional"))
      (node (ref "IC37") (pin "9") (pinfunction "4Q_9") (pintype "tri_state"))
      (node (ref "JP3") (pin "4") (pinfunction "4_4") (pintype "passive"))
    )
    (net (code "7") (name "ADDRESS4") (class "Default")
      (node (ref "IC35") (pin "14") (pinfunction "B5_14") (pintype "bidirectional"))
      (node (ref "IC37") (pin "12") (pinfunction "5Q_12") (pintype "tri_state"))
      (node (ref "JP3") (pin "5") (pinfunction "5_5") (pintype "passive"))
    )
    (net (code "8") (name "ADDRESS5") (class "Default")
      (node (ref "IC35") (pin "13") (pinfunction "B6_13") (pintype "bidirectional"))
      (node (ref "IC37") (pin "15") (pinfunction "6Q_15") (pintype "tri_state"))
      (node (ref "JP3") (pin "6") (pinfunction "6_6") (pintype "passive"))
    )
    (net (code "9") (name "ADDRESS6") (class "Default")
      (node (ref "IC35") (pin "12") (pinfunction "B7_12") (pintype "bidirectional"))
      (node (ref "IC37") (pin "16") (pinfunction "7Q_16") (pintype "tri_state"))
      (node (ref "JP3") (pin "7") (pinfunction "7_7") (pintype "passive"))
    )
    (net (code "10") (name "ADDRESS7") (class "Default")
      (node (ref "IC35") (pin "11") (pinfunction "B8_11") (pintype "bidirectional"))
      (node (ref "IC37") (pin "19") (pinfunction "8Q_19") (pintype "tri_state"))
      (node (ref "JP3") (pin "8") (pinfunction "8_8") (pintype "passive"))
    )
    (net (code "11") (name "ADDRESS8") (class "Default")
      (node (ref "IC36") (pin "18") (pinfunction "B1_18") (pintype "bidirectional"))
      (node (ref "IC38") (pin "3") (pinfunction "Q0_3") (pintype "output"))
      (node (ref "JP3") (pin "9") (pinfunction "9_9") (pintype "passive"))
    )
    (net (code "12") (name "ADDRESS9") (class "Default")
      (node (ref "IC36") (pin "17") (pinfunction "B2_17") (pintype "bidirectional"))
      (node (ref "IC38") (pin "4") (pinfunction "Q1_4") (pintype "output"))
      (node (ref "JP3") (pin "10") (pinfunction "10_10") (pintype "passive"))
    )
    (net (code "13") (name "ADDRESS10") (class "Default")
      (node (ref "IC36") (pin "16") (pinfunction "B3_16") (pintype "bidirectional"))
      (node (ref "IC38") (pin "5") (pinfunction "Q2_5") (pintype "output"))
      (node (ref "JP3") (pin "11") (pinfunction "11_11") (pintype "passive"))
    )
    (net (code "14") (name "ALUFLAGOUT") (class "Default")
      (node (ref "IC19") (pin "11") (pinfunction "O_11") (pintype "output"))
      (node (ref "IC49") (pin "4") (pinfunction "S0_4") (pintype "input"))
    )
    (net (code "15") (name "BUFFERTODATABUS") (class "Default")
      (node (ref "IC22") (pin "6") (pinfunction "O_6") (pintype "output"))
      (node (ref "IC27") (pin "12") (pinfunction "S2_12") (pintype "input"))
    )
    (net (code "16") (name "CUREAD") (class "Default")
      (node (ref "IC2") (pin "2") (pinfunction "Q0_2") (pintype "output"))
      (node (ref "IC26") (pin "1") (pinfunction "I0_1") (pintype "input"))
    )
    (net (code "17") (name "D0") (class "Default")
      (node (ref "IC28") (pin "3") (pinfunction "1D_3") (pintype "input"))
      (node (ref "IC30") (pin "3") (pinfunction "O_3") (pintype "output"))
      (node (ref "JP2") (pin "8") (pinfunction "8_8") (pintype "passive"))
    )
    (net (code "18") (name "D1") (class "Default")
      (node (ref "IC28") (pin "4") (pinfunction "2D_4") (pintype "input"))
      (node (ref "IC30") (pin "6") (pinfunction "O_6") (pintype "output"))
      (node (ref "JP2") (pin "9") (pinfunction "9_9") (pintype "passive"))
    )
    (net (code "19") (name "D2") (class "Default")
      (node (ref "IC28") (pin "7") (pinfunction "3D_7") (pintype "input"))
      (node (ref "IC30") (pin "8") (pinfunction "O_8") (pintype "output"))
      (node (ref "JP2") (pin "10") (pinfunction "10_10") (pintype "passive"))
    )
    (net (code "20") (name "D3") (class "Default")
      (node (ref "IC28") (pin "8") (pinfunction "4D_8") (pintype "input"))
      (node (ref "IC30") (pin "11") (pinfunction "O_11") (pintype "output"))
      (node (ref "JP2") (pin "11") (pinfunction "11_11") (pintype "passive"))
    )
    (net (code "21") (name "D4") (class "Default")
      (node (ref "IC28") (pin "13") (pinfunction "5D_13") (pintype "input"))
      (node (ref "JP2") (pin "12") (pinfunction "12_12") (pintype "passive"))
    )
    (net (code "22") (name "D5") (class "Default")
      (node (ref "IC28") (pin "14") (pinfunction "6D_14") (pintype "input"))
      (node (ref "JP2") (pin "13") (pinfunction "13_13") (pintype "passive"))
    )
    (net (code "23") (name "D6") (class "Default")
      (node (ref "IC28") (pin "17") (pinfunction "7D_17") (pintype "input"))
      (node (ref "JP2") (pin "14") (pinfunction "14_14") (pintype "passive"))
    )
    (net (code "24") (name "D7") (class "Default")
      (node (ref "IC28") (pin "18") (pinfunction "8D_18") (pintype "input"))
      (node (ref "JP2") (pin "15") (pinfunction "15_15") (pintype "passive"))
    )
    (net (code "25") (name "D8") (class "Default")
      (node (ref "IC25") (pin "14") (pinfunction "D0_14") (pintype "input"))
      (node (ref "JP2") (pin "16") (pinfunction "16_16") (pintype "passive"))
    )
    (net (code "26") (name "D9") (class "Default")
      (node (ref "IC25") (pin "13") (pinfunction "D1_13") (pintype "input"))
      (node (ref "JP2") (pin "17") (pinfunction "17_17") (pintype "passive"))
    )
    (net (code "27") (name "D10") (class "Default")
      (node (ref "IC25") (pin "12") (pinfunction "D2_12") (pintype "input"))
      (node (ref "JP2") (pin "18") (pinfunction "18_18") (pintype "passive"))
    )
    (net (code "28") (name "DATABUS0") (class "Default")
      (node (ref "IC28") (pin "2") (pinfunction "1Q_2") (pintype "tri_state"))
      (node (ref "IC30") (pin "2") (pinfunction "I_2") (pintype "input"))
      (node (ref "IC32") (pin "18") (pinfunction "B1_18") (pintype "bidirectional"))
      (node (ref "IC37") (pin "3") (pinfunction "1D_3") (pintype "input"))
      (node (ref "IC42") (pin "4") (pinfunction "D0_4") (pintype "input"))
      (node (ref "IC43") (pin "4") (pinfunction "D0_4") (pintype "input"))
      (node (ref "IC47") (pin "18") (pinfunction "B1_18") (pintype "bidirectional"))
      (node (ref "IC50") (pin "3") (pinfunction "Q0_3") (pintype "output"))
      (node (ref "IC58") (pin "18") (pinfunction "B1_18") (pintype "bidirectional"))
      (node (ref "IC60") (pin "3") (pinfunction "1D_3") (pintype "input"))
      (node (ref "IC63") (pin "14") (pinfunction "D0_14") (pintype "input"))
      (node (ref "IC63") (pin "3") (pinfunction "Q0_3") (pintype "output"))
      (node (ref "IC64") (pin "14") (pinfunction "D0_14") (pintype "input"))
      (node (ref "IC64") (pin "3") (pinfunction "Q0_3") (pintype "output"))
      (node (ref "IC65") (pin "2") (pinfunction "1Q_2") (pintype "tri_state"))
      (node (ref "IC65") (pin "3") (pinfunction "1D_3") (pintype "input"))
      (node (ref "IC66") (pin "2") (pinfunction "1Q_2") (pintype "tri_state"))
      (node (ref "IC66") (pin "3") (pinfunction "1D_3") (pintype "input"))
      (node (ref "V1") (pin "15") (pinfunction "A_15") (pintype "input"))
    )
    (net (code "29") (name "DATABUS1") (class "Default")
      (node (ref "IC28") (pin "5") (pinfunction "2Q_5") (pintype "tri_state"))
      (node (ref "IC30") (pin "5") (pinfunction "I_5") (pintype "input"))
      (node (ref "IC32") (pin "17") (pinfunction "B2_17") (pintype "bidirectional"))
      (node (ref "IC37") (pin "4") (pinfunction "2D_4") (pintype "input"))
      (node (ref "IC42") (pin "7") (pinfunction "D1_7") (pintype "input"))
      (node (ref "IC43") (pin "7") (pinfunction "D1_7") (pintype "input"))
      (node (ref "IC47") (pin "17") (pinfunction "B2_17") (pintype "bidirectional"))
      (node (ref "IC50") (pin "4") (pinfunction "Q1_4") (pintype "output"))
      (node (ref "IC58") (pin "17") (pinfunction "B2_17") (pintype "bidirectional"))
      (node (ref "IC60") (pin "4") (pinfunction "2D_4") (pintype "input"))
      (node (ref "IC63") (pin "13") (pinfunction "D1_13") (pintype "input"))
      (node (ref "IC63") (pin "4") (pinfunction "Q1_4") (pintype "output"))
      (node (ref "IC64") (pin "13") (pinfunction "D1_13") (pintype "input"))
      (node (ref "IC64") (pin "4") (pinfunction "Q1_4") (pintype "output"))
      (node (ref "IC65") (pin "4") (pinfunction "2D_4") (pintype "input"))
      (node (ref "IC65") (pin "5") (pinfunction "2Q_5") (pintype "tri_state"))
      (node (ref "IC66") (pin "4") (pinfunction "2D_4") (pintype "input"))
      (node (ref "IC66") (pin "5") (pinfunction "2Q_5") (pintype "tri_state"))
      (node (ref "V1") (pin "1") (pinfunction "B_1") (pintype "input"))
    )
    (net (code "30") (name "DATABUS2") (class "Default")
      (node (ref "IC28") (pin "6") (pinfunction "3Q_6") (pintype "tri_state"))
      (node (ref "IC30") (pin "9") (pinfunction "I_9") (pintype "input"))
      (node (ref "IC32") (pin "16") (pinfunction "B3_16") (pintype "bidirectional"))
      (node (ref "IC37") (pin "7") (pinfunction "3D_7") (pintype "input"))
      (node (ref "IC42") (pin "13") (pinfunction "D2_13") (pintype "input"))
      (node (ref "IC43") (pin "13") (pinfunction "D2_13") (pintype "input"))
      (node (ref "IC47") (pin "16") (pinfunction "B3_16") (pintype "bidirectional"))
      (node (ref "IC50") (pin "5") (pinfunction "Q2_5") (pintype "output"))
      (node (ref "IC58") (pin "16") (pinfunction "B3_16") (pintype "bidirectional"))
      (node (ref "IC60") (pin "7") (pinfunction "3D_7") (pintype "input"))
      (node (ref "IC63") (pin "12") (pinfunction "D2_12") (pintype "input"))
      (node (ref "IC63") (pin "5") (pinfunction "Q2_5") (pintype "output"))
      (node (ref "IC64") (pin "12") (pinfunction "D2_12") (pintype "input"))
      (node (ref "IC64") (pin "5") (pinfunction "Q2_5") (pintype "output"))
      (node (ref "IC65") (pin "6") (pinfunction "3Q_6") (pintype "tri_state"))
      (node (ref "IC65") (pin "7") (pinfunction "3D_7") (pintype "input"))
      (node (ref "IC66") (pin "6") (pinfunction "3Q_6") (pintype "tri_state"))
      (node (ref "IC66") (pin "7") (pinfunction "3D_7") (pintype "input"))
      (node (ref "V1") (pin "10") (pinfunction "C_10") (pintype "input"))
    )
    (net (code "31") (name "DATABUS3") (class "Default")
      (node (ref "IC28") (pin "9") (pinfunction "4Q_9") (pintype "tri_state"))
      (node (ref "IC30") (pin "12") (pinfunction "I_12") (pintype "input"))
      (node (ref "IC32") (pin "15") (pinfunction "B4_15") (pintype "bidirectional"))
      (node (ref "IC37") (pin "8") (pinfunction "4D_8") (pintype "input"))
      (node (ref "IC42") (pin "14") (pinfunction "D3_14") (pintype "input"))
      (node (ref "IC43") (pin "14") (pinfunction "D3_14") (pintype "input"))
      (node (ref "IC47") (pin "15") (pinfunction "B4_15") (pintype "bidirectional"))
      (node (ref "IC50") (pin "6") (pinfunction "Q3_6") (pintype "output"))
      (node (ref "IC58") (pin "15") (pinfunction "B4_15") (pintype "bidirectional"))
      (node (ref "IC60") (pin "8") (pinfunction "4D_8") (pintype "input"))
      (node (ref "IC63") (pin "11") (pinfunction "D3_11") (pintype "input"))
      (node (ref "IC63") (pin "6") (pinfunction "Q3_6") (pintype "output"))
      (node (ref "IC64") (pin "11") (pinfunction "D3_11") (pintype "input"))
      (node (ref "IC64") (pin "6") (pinfunction "Q3_6") (pintype "output"))
      (node (ref "IC65") (pin "8") (pinfunction "4D_8") (pintype "input"))
      (node (ref "IC65") (pin "9") (pinfunction "4Q_9") (pintype "tri_state"))
      (node (ref "IC66") (pin "8") (pinfunction "4D_8") (pintype "input"))
      (node (ref "IC66") (pin "9") (pinfunction "4Q_9") (pintype "tri_state"))
      (node (ref "V1") (pin "9") (pinfunction "D_9") (pintype "input"))
    )
    (net (code "32") (name "DATABUS4") (class "Default")
      (node (ref "IC28") (pin "12") (pinfunction "5Q_12") (pintype "tri_state"))
      (node (ref "IC32") (pin "14") (pinfunction "B5_14") (pintype "bidirectional"))
      (node (ref "IC37") (pin "13") (pinfunction "5D_13") (pintype "input"))
      (node (ref "IC47") (pin "14") (pinfunction "B5_14") (pintype "bidirectional"))
      (node (ref "IC58") (pin "14") (pinfunction "B5_14") (pintype "bidirectional"))
      (node (ref "IC60") (pin "13") (pinfunction "5D_13") (pintype "input"))
      (node (ref "IC65") (pin "12") (pinfunction "5Q_12") (pintype "tri_state"))
      (node (ref "IC65") (pin "13") (pinfunction "5D_13") (pintype "input"))
      (node (ref "IC66") (pin "12") (pinfunction "5Q_12") (pintype "tri_state"))
      (node (ref "IC66") (pin "13") (pinfunction "5D_13") (pintype "input"))
      (node (ref "V2") (pin "15") (pinfunction "A_15") (pintype "input"))
    )
    (net (code "33") (name "DATABUS5") (class "Default")
      (node (ref "IC28") (pin "15") (pinfunction "6Q_15") (pintype "tri_state"))
      (node (ref "IC32") (pin "13") (pinfunction "B6_13") (pintype "bidirectional"))
      (node (ref "IC37") (pin "14") (pinfunction "6D_14") (pintype "input"))
      (node (ref "IC66") (pin "14") (pinfunction "6D_14") (pintype "input"))
      (node (ref "IC66") (pin "15") (pinfunction "6Q_15") (pintype "tri_state"))
      (node (ref "V2") (pin "1") (pinfunction "B_1") (pintype "input"))
    )
    (net (code "34") (name "DATABUS6") (class "Default")
      (node (ref "IC28") (pin "16") (pinfunction "7Q_16") (pintype "tri_state"))
      (node (ref "IC32") (pin "12") (pinfunction "B7_12") (pintype "bidirectional"))
      (node (ref "IC37") (pin "17") (pinfunction "7D_17") (pintype "input"))
      (node (ref "IC66") (pin "16") (pinfunction "7Q_16") (pintype "tri_state"))
      (node (ref "IC66") (pin "17") (pinfunction "7D_17") (pintype "input"))
      (node (ref "V2") (pin "10") (pinfunction "C_10") (pintype "input"))
    )
    (net (code "35") (name "DATABUS7") (class "Default")
      (node (ref "IC28") (pin "19") (pinfunction "8Q_19") (pintype "tri_state"))
      (node (ref "IC32") (pin "11") (pinfunction "B8_11") (pintype "bidirectional"))
      (node (ref "IC37") (pin "18") (pinfunction "8D_18") (pintype "input"))
      (node (ref "IC66") (pin "18") (pinfunction "8D_18") (pintype "input"))
      (node (ref "IC66") (pin "19") (pinfunction "8Q_19") (pintype "tri_state"))
      (node (ref "V2") (pin "9") (pinfunction "D_9") (pintype "input"))
    )
    (net (code "36") (name "DATABUS8") (class "Default")
      (node (ref "IC25") (pin "3") (pinfunction "Q0_3") (pintype "output"))
      (node (ref "IC33") (pin "18") (pinfunction "B1_18") (pintype "bidirectional"))
      (node (ref "IC38") (pin "14") (pinfunction "D0_14") (pintype "input"))
      (node (ref "IC67") (pin "14") (pinfunction "D0_14") (pintype "input"))
      (node (ref "IC67") (pin "3") (pinfunction "Q0_3") (pintype "output"))
      (node (ref "V3") (pin "15") (pinfunction "A_15") (pintype "input"))
    )
    (net (code "37") (name "DATABUS9") (class "Default")
      (node (ref "IC25") (pin "4") (pinfunction "Q1_4") (pintype "output"))
      (node (ref "IC33") (pin "17") (pinfunction "B2_17") (pintype "bidirectional"))
      (node (ref "IC38") (pin "13") (pinfunction "D1_13") (pintype "input"))
      (node (ref "IC67") (pin "13") (pinfunction "D1_13") (pintype "input"))
      (node (ref "IC67") (pin "4") (pinfunction "Q1_4") (pintype "output"))
      (node (ref "V3") (pin "1") (pinfunction "B_1") (pintype "input"))
    )
    (net (code "38") (name "DATABUS10") (class "Default")
      (node (ref "IC25") (pin "5") (pinfunction "Q2_5") (pintype "output"))
      (node (ref "IC33") (pin "16") (pinfunction "B3_16") (pintype "bidirectional"))
      (node (ref "IC38") (pin "12") (pinfunction "D2_12") (pintype "input"))
      (node (ref "IC67") (pin "12") (pinfunction "D2_12") (pintype "input"))
      (node (ref "IC67") (pin "5") (pinfunction "Q2_5") (pintype "output"))
      (node (ref "V3") (pin "10") (pinfunction "C_10") (pintype "input"))
    )
    (net (code "39") (name "DATABUSTORAM") (class "Default")
      (node (ref "IC22") (pin "8") (pinfunction "O_8") (pintype "output"))
      (node (ref "IC27") (pin "6") (pinfunction "S1_6") (pintype "input"))
    )
    (net (code "40") (name "DECODECLOCK") (class "Default")
      (node (ref "IC4") (pin "6") (pinfunction "O_6") (pintype "output"))
      (node (ref "IC7") (pin "14") (pinfunction "CLK_14") (pintype "input"))
    )
    (net (code "41") (name "EEPROMOUT") (class "Default")
      (node (ref "IC16") (pin "10") (pinfunction "I1_10") (pintype "input"))
      (node (ref "IC16") (pin "13") (pinfunction "I1_13") (pintype "input"))
      (node (ref "IC16") (pin "2") (pinfunction "I1_2") (pintype "input"))
      (node (ref "IC16") (pin "5") (pinfunction "I1_5") (pintype "input"))
      (node (ref "IC17") (pin "10") (pinfunction "I1_10") (pintype "input"))
      (node (ref "IC17") (pin "13") (pinfunction "I1_13") (pintype "input"))
      (node (ref "IC17") (pin "2") (pinfunction "I1_2") (pintype "input"))
      (node (ref "IC17") (pin "5") (pinfunction "I1_5") (pintype "input"))
      (node (ref "IC18") (pin "10") (pinfunction "I1_10") (pintype "input"))
      (node (ref "IC18") (pin "13") (pinfunction "I1_13") (pintype "input"))
      (node (ref "IC18") (pin "2") (pinfunction "I1_2") (pintype "input"))
      (node (ref "IC18") (pin "5") (pinfunction "I1_5") (pintype "input"))
      (node (ref "IC19") (pin "10") (pinfunction "I1_10") (pintype "input"))
      (node (ref "IC19") (pin "13") (pinfunction "I1_13") (pintype "input"))
      (node (ref "IC19") (pin "2") (pinfunction "I1_2") (pintype "input"))
      (node (ref "IC19") (pin "5") (pinfunction "I1_5") (pintype "input"))
      (node (ref "IC20") (pin "10") (pinfunction "I1_10") (pintype "input"))
      (node (ref "IC20") (pin "13") (pinfunction "I1_13") (pintype "input"))
      (node (ref "IC20") (pin "2") (pinfunction "I1_2") (pintype "input"))
      (node (ref "IC20") (pin "5") (pinfunction "I1_5") (pintype "input"))
      (node (ref "IC21") (pin "10") (pinfunction "I1_10") (pintype "input"))
      (node (ref "IC21") (pin "13") (pinfunction "I1_13") (pintype "input"))
      (node (ref "IC21") (pin "2") (pinfunction "I1_2") (pintype "input"))
      (node (ref "IC21") (pin "5") (pinfunction "I1_5") (pintype "input"))
      (node (ref "IC22") (pin "10") (pinfunction "I1_10") (pintype "input"))
      (node (ref "IC22") (pin "13") (pinfunction "I1_13") (pintype "input"))
      (node (ref "IC22") (pin "2") (pinfunction "I1_2") (pintype "input"))
      (node (ref "IC22") (pin "5") (pinfunction "I1_5") (pintype "input"))
      (node (ref "IC23") (pin "10") (pinfunction "I1_10") (pintype "input"))
      (node (ref "IC23") (pin "13") (pinfunction "I1_13") (pintype "input"))
      (node (ref "IC23") (pin "2") (pinfunction "I1_2") (pintype "input"))
      (node (ref "IC23") (pin "5") (pinfunction "I1_5") (pintype "input"))
      (node (ref "IC24") (pin "10") (pinfunction "I1_10") (pintype "input"))
      (node (ref "IC24") (pin "13") (pinfunction "I1_13") (pintype "input"))
      (node (ref "IC24") (pin "2") (pinfunction "I1_2") (pintype "input"))
      (node (ref "IC24") (pin "5") (pinfunction "I1_5") (pintype "input"))
      (node (ref "IC7") (pin "2") (pinfunction "Q1_2") (pintype "output"))
    )
    (net (code "42") (name "EEPROMRESET") (class "Default")
      (node (ref "IC15") (pin "10") (pinfunction "D1_10") (pintype "tri_state"))
      (node (ref "IC9") (pin "2") (pinfunction "D_2") (pintype "input"))
    )
    (net (code "43") (name "FLAGJSRLATCH") (class "Default")
      (node (ref "IC20") (pin "11") (pinfunction "O_11") (pintype "output"))
      (node (ref "IC65") (pin "11") (pinfunction "CLK_11") (pintype "input"))
    )
    (net (code "44") (name "FLAGJSROUTPUT") (class "Default")
      (node (ref "IC20") (pin "8") (pinfunction "O_8") (pintype "output"))
      (node (ref "IC61") (pin "12") (pinfunction "S2_12") (pintype "input"))
    )
    (net (code "45") (name "FLAGLATCH") (class "Default")
      (node (ref "IC19") (pin "8") (pinfunction "O_8") (pintype "output"))
      (node (ref "IC60") (pin "11") (pinfunction "CLK_11") (pintype "input"))
    )
    (net (code "46") (name "FLAGOUTPUT") (class "Default")
      (node (ref "IC19") (pin "6") (pinfunction "O_6") (pintype "output"))
      (node (ref "IC56") (pin "4") (pinfunction "S0_4") (pintype "input"))
    )
    (net (code "47") (name "FUNCTION0") (class "Default")
      (node (ref "IC17") (pin "6") (pinfunction "O_6") (pintype "output"))
      (node (ref "IC48") (pin "14") (pinfunction "S3_14") (pintype "input"))
    )
    (net (code "48") (name "FUNCTION1") (class "Default")
      (node (ref "IC17") (pin "3") (pinfunction "O_3") (pintype "output"))
      (node (ref "IC48") (pin "12") (pinfunction "S2_12") (pintype "input"))
    )
    (net (code "49") (name "FUNCTION2") (class "Default")
      (node (ref "IC16") (pin "11") (pinfunction "O_11") (pintype "output"))
      (node (ref "IC48") (pin "6") (pinfunction "S1_6") (pintype "input"))
    )
    (net (code "50") (name "FUNCTION3") (class "Default")
      (node (ref "IC16") (pin "8") (pinfunction "O_8") (pintype "output"))
      (node (ref "IC48") (pin "4") (pinfunction "S0_4") (pintype "input"))
    )
    (net (code "51") (name "IOLATCH") (class "Default")
      (node (ref "IC1") (pin "4") (pinfunction "Q2_4") (pintype "output"))
      (node (ref "IC26") (pin "10") (pinfunction "I1_10") (pintype "input"))
      (node (ref "IC29") (pin "11") (pinfunction "CLK_11") (pintype "input"))
    )
    (net (code "52") (name "LATCHRESET") (class "Default")
      (node (ref "IC24") (pin "6") (pinfunction "O_6") (pintype "output"))
      (node (ref "IC26") (pin "5") (pinfunction "I1_5") (pintype "input"))
      (node (ref "IC40") (pin "5") (pinfunction "I1_5") (pintype "input"))
      (node (ref "IC45") (pin "5") (pinfunction "I1_5") (pintype "input"))
      (node (ref "IC55") (pin "1") (pinfunction "I0_1") (pintype "input"))
      (node (ref "IC62") (pin "2") (pinfunction "I1_2") (pintype "input"))
    )
    (net (code "53") (name "MICROCODELATCH") (class "Default")
      (node (ref "IC22") (pin "3") (pinfunction "O_3") (pintype "output"))
      (node (ref "IC26") (pin "9") (pinfunction "I0_9") (pintype "input"))
    )
    (net (code "54") (name "MICROCODERAMREAD") (class "Default")
      (node (ref "IC24") (pin "11") (pinfunction "O_11") (pintype "output"))
      (node (ref "IC27") (pin "4") (pinfunction "S0_4") (pintype "input"))
    )
    (net (code "55") (name "Net-(IC1A-CLK)") (class "Default")
      (node (ref "IC1") (pin "14") (pinfunction "CLK_14") (pintype "input"))
      (node (ref "IC3") (pin "3") (pinfunction "O_3") (pintype "output"))
    )
    (net (code "56") (name "Net-(IC1A-Q1)") (class "Default")
      (node (ref "IC1") (pin "2") (pinfunction "Q1_2") (pintype "output"))
      (node (ref "IC2") (pin "4") (pinfunction "S0_4") (pintype "input"))
    )
    (net (code "57") (name "Net-(IC1A-Q3)") (class "Default")
      (node (ref "IC1") (pin "7") (pinfunction "Q3_7") (pintype "output"))
      (node (ref "IC3") (pin "5") (pinfunction "I1_5") (pintype "input"))
    )
    (net (code "58") (name "Net-(IC1A-Q5)") (class "Default")
      (node (ref "IC1") (pin "1") (pinfunction "Q5_1") (pintype "output"))
      (node (ref "IC4") (pin "5") (pinfunction "I1_5") (pintype "input"))
      (node (ref "IC5") (pin "1") (pinfunction "I_1") (pintype "input"))
    )
    (net (code "59") (name "Net-(IC1A-Q7)") (class "Default")
      (node (ref "IC1") (pin "6") (pinfunction "Q7_6") (pintype "output"))
      (node (ref "IC3") (pin "10") (pinfunction "I1_10") (pintype "input"))
    )
    (net (code "60") (name "Net-(IC1A-RES)") (class "Default")
      (node (ref "IC1") (pin "15") (pinfunction "RES_15") (pintype "input"))
      (node (ref "IC3") (pin "8") (pinfunction "O_8") (pintype "output"))
    )
    (net (code "61") (name "Net-(IC2A-Q1)") (class "Default")
      (node (ref "IC2") (pin "9") (pinfunction "Q1_9") (pintype "output"))
      (node (ref "IC4") (pin "9") (pinfunction "I0_9") (pintype "input"))
    )
    (net (code "62") (name "Net-(IC2A-R0)") (class "Default")
      (node (ref "IC2") (pin "3") (pinfunction "R0_3") (pintype "input"))
      (node (ref "IC3") (pin "6") (pinfunction "O_6") (pintype "output"))
    )
    (net (code "63") (name "Net-(IC2A-R1)") (class "Default")
      (node (ref "IC2") (pin "7") (pinfunction "R1_7") (pintype "input"))
      (node (ref "IC3") (pin "11") (pinfunction "O_11") (pintype "output"))
    )
    (net (code "64") (name "Net-(IC3A-I0)") (class "Default")
      (node (ref "IC3") (pin "1") (pinfunction "I0_1") (pintype "input"))
      (node (ref "IC4") (pin "3") (pinfunction "O_3") (pintype "output"))
    )
    (net (code "65") (name "Net-(IC4A-I0)") (class "Default")
      (node (ref "IC4") (pin "1") (pinfunction "I0_1") (pintype "input"))
      (node (ref "IC5") (pin "2") (pinfunction "O_2") (pintype "output"))
    )
    (net (code "66") (name "Net-(IC4A-I1)") (class "Default")
      (node (ref "IC4") (pin "2") (pinfunction "I1_2") (pintype "input"))
      (node (ref "IC4") (pin "4") (pinfunction "I0_4") (pintype "input"))
      (node (ref "IC4") (pin "8") (pinfunction "O_8") (pintype "output"))
    )
    (net (code "67") (name "Net-(IC6A-P1)") (class "Default")
      (node (ref "IC6") (pin "10") (pinfunction "P1_10") (pintype "input"))
      (node (ref "IC7") (pin "7") (pinfunction "Q3_7") (pintype "output"))
    )
    (net (code "68") (name "Net-(IC6A-RES)") (class "Default")
      (node (ref "IC6") (pin "11") (pinfunction "RES_11") (pintype "input"))
      (node (ref "IC8") (pin "1") (pinfunction "I0_1") (pintype "input"))
      (node (ref "IC8") (pin "6") (pinfunction "O_6") (pintype "output"))
    )
    (net (code "69") (name "Net-(IC7A-Q5)") (class "Default")
      (node (ref "IC7") (pin "1") (pinfunction "Q5_1") (pintype "output"))
      (node (ref "IC8") (pin "2") (pinfunction "I1_2") (pintype "input"))
    )
    (net (code "70") (name "Net-(IC7A-RES)") (class "Default")
      (node (ref "IC7") (pin "15") (pinfunction "RES_15") (pintype "input"))
      (node (ref "IC8") (pin "3") (pinfunction "O_3") (pintype "output"))
    )
    (net (code "71") (name "Net-(IC10A-O)") (class "Default")
      (node (ref "IC10") (pin "2") (pinfunction "O_2") (pintype "output"))
      (node (ref "IC9") (pin "3") (pinfunction "CLK_3") (pintype "input"))
    )
    (net (code "72") (name "Net-(IC10B-O)") (class "Default")
      (node (ref "IC10") (pin "4") (pinfunction "O_4") (pintype "output"))
      (node (ref "IC9") (pin "1") (pinfunction "CLR_1") (pintype "input"))
    )
    (net (code "73") (name "Net-(IC11-D0)") (class "Default")
      (node (ref "IC11") (pin "9") (pinfunction "D0_9") (pintype "tri_state"))
      (node (ref "IC16") (pin "1") (pinfunction "I0_1") (pintype "input"))
    )
    (net (code "74") (name "Net-(IC11-D1)") (class "Default")
      (node (ref "IC11") (pin "10") (pinfunction "D1_10") (pintype "tri_state"))
      (node (ref "IC16") (pin "4") (pinfunction "I0_4") (pintype "input"))
    )
    (net (code "75") (name "Net-(IC11-D2)") (class "Default")
      (node (ref "IC11") (pin "11") (pinfunction "D2_11") (pintype "tri_state"))
      (node (ref "IC16") (pin "9") (pinfunction "I0_9") (pintype "input"))
    )
    (net (code "76") (name "Net-(IC11-D3)") (class "Default")
      (node (ref "IC11") (pin "13") (pinfunction "D3_13") (pintype "tri_state"))
      (node (ref "IC16") (pin "12") (pinfunction "I0_12") (pintype "input"))
    )
    (net (code "77") (name "Net-(IC11-D4)") (class "Default")
      (node (ref "IC11") (pin "14") (pinfunction "D4_14") (pintype "tri_state"))
      (node (ref "IC17") (pin "1") (pinfunction "I0_1") (pintype "input"))
    )
    (net (code "78") (name "Net-(IC11-D5)") (class "Default")
      (node (ref "IC11") (pin "15") (pinfunction "D5_15") (pintype "tri_state"))
      (node (ref "IC17") (pin "4") (pinfunction "I0_4") (pintype "input"))
    )
    (net (code "79") (name "Net-(IC11-D6)") (class "Default")
      (node (ref "IC11") (pin "16") (pinfunction "D6_16") (pintype "tri_state"))
      (node (ref "IC17") (pin "9") (pinfunction "I0_9") (pintype "input"))
    )
    (net (code "80") (name "Net-(IC11-D7)") (class "Default")
      (node (ref "IC11") (pin "17") (pinfunction "D7_17") (pintype "tri_state"))
      (node (ref "IC17") (pin "12") (pinfunction "I0_12") (pintype "input"))
    )
    (net (code "81") (name "Net-(IC12-D0)") (class "Default")
      (node (ref "IC12") (pin "9") (pinfunction "D0_9") (pintype "tri_state"))
      (node (ref "IC18") (pin "1") (pinfunction "I0_1") (pintype "input"))
    )
    (net (code "82") (name "Net-(IC12-D1)") (class "Default")
      (node (ref "IC12") (pin "10") (pinfunction "D1_10") (pintype "tri_state"))
      (node (ref "IC18") (pin "4") (pinfunction "I0_4") (pintype "input"))
    )
    (net (code "83") (name "Net-(IC12-D2)") (class "Default")
      (node (ref "IC12") (pin "11") (pinfunction "D2_11") (pintype "tri_state"))
      (node (ref "IC18") (pin "9") (pinfunction "I0_9") (pintype "input"))
    )
    (net (code "84") (name "Net-(IC12-D3)") (class "Default")
      (node (ref "IC12") (pin "13") (pinfunction "D3_13") (pintype "tri_state"))
      (node (ref "IC18") (pin "12") (pinfunction "I0_12") (pintype "input"))
    )
    (net (code "85") (name "Net-(IC12-D4)") (class "Default")
      (node (ref "IC12") (pin "14") (pinfunction "D4_14") (pintype "tri_state"))
      (node (ref "IC19") (pin "1") (pinfunction "I0_1") (pintype "input"))
    )
    (net (code "86") (name "Net-(IC12-D5)") (class "Default")
      (node (ref "IC12") (pin "15") (pinfunction "D5_15") (pintype "tri_state"))
      (node (ref "IC19") (pin "4") (pinfunction "I0_4") (pintype "input"))
    )
    (net (code "87") (name "Net-(IC12-D6)") (class "Default")
      (node (ref "IC12") (pin "16") (pinfunction "D6_16") (pintype "tri_state"))
      (node (ref "IC19") (pin "9") (pinfunction "I0_9") (pintype "input"))
    )
    (net (code "88") (name "Net-(IC12-D7)") (class "Default")
      (node (ref "IC12") (pin "17") (pinfunction "D7_17") (pintype "tri_state"))
      (node (ref "IC19") (pin "12") (pinfunction "I0_12") (pintype "input"))
    )
    (net (code "89") (name "Net-(IC13-D0)") (class "Default")
      (node (ref "IC13") (pin "9") (pinfunction "D0_9") (pintype "tri_state"))
      (node (ref "IC20") (pin "1") (pinfunction "I0_1") (pintype "input"))
    )
    (net (code "90") (name "Net-(IC13-D1)") (class "Default")
      (node (ref "IC13") (pin "10") (pinfunction "D1_10") (pintype "tri_state"))
      (node (ref "IC20") (pin "4") (pinfunction "I0_4") (pintype "input"))
    )
    (net (code "91") (name "Net-(IC13-D2)") (class "Default")
      (node (ref "IC13") (pin "11") (pinfunction "D2_11") (pintype "tri_state"))
      (node (ref "IC20") (pin "9") (pinfunction "I0_9") (pintype "input"))
    )
    (net (code "92") (name "Net-(IC13-D3)") (class "Default")
      (node (ref "IC13") (pin "13") (pinfunction "D3_13") (pintype "tri_state"))
      (node (ref "IC20") (pin "12") (pinfunction "I0_12") (pintype "input"))
    )
    (net (code "93") (name "Net-(IC13-D4)") (class "Default")
      (node (ref "IC13") (pin "14") (pinfunction "D4_14") (pintype "tri_state"))
      (node (ref "IC21") (pin "1") (pinfunction "I0_1") (pintype "input"))
    )
    (net (code "94") (name "Net-(IC13-D5)") (class "Default")
      (node (ref "IC13") (pin "15") (pinfunction "D5_15") (pintype "tri_state"))
      (node (ref "IC21") (pin "4") (pinfunction "I0_4") (pintype "input"))
    )
    (net (code "95") (name "Net-(IC13-D6)") (class "Default")
      (node (ref "IC13") (pin "16") (pinfunction "D6_16") (pintype "tri_state"))
      (node (ref "IC21") (pin "9") (pinfunction "I0_9") (pintype "input"))
    )
    (net (code "96") (name "Net-(IC13-D7)") (class "Default")
      (node (ref "IC13") (pin "17") (pinfunction "D7_17") (pintype "tri_state"))
      (node (ref "IC21") (pin "12") (pinfunction "I0_12") (pintype "input"))
    )
    (net (code "97") (name "Net-(IC14-D0)") (class "Default")
      (node (ref "IC14") (pin "9") (pinfunction "D0_9") (pintype "tri_state"))
      (node (ref "IC22") (pin "1") (pinfunction "I0_1") (pintype "input"))
    )
    (net (code "98") (name "Net-(IC14-D1)") (class "Default")
      (node (ref "IC14") (pin "10") (pinfunction "D1_10") (pintype "tri_state"))
      (node (ref "IC22") (pin "4") (pinfunction "I0_4") (pintype "input"))
    )
    (net (code "99") (name "Net-(IC14-D2)") (class "Default")
      (node (ref "IC14") (pin "11") (pinfunction "D2_11") (pintype "tri_state"))
      (node (ref "IC22") (pin "9") (pinfunction "I0_9") (pintype "input"))
    )
    (net (code "100") (name "Net-(IC14-D3)") (class "Default")
      (node (ref "IC14") (pin "13") (pinfunction "D3_13") (pintype "tri_state"))
      (node (ref "IC22") (pin "12") (pinfunction "I0_12") (pintype "input"))
    )
    (net (code "101") (name "Net-(IC14-D4)") (class "Default")
      (node (ref "IC14") (pin "14") (pinfunction "D4_14") (pintype "tri_state"))
      (node (ref "IC23") (pin "1") (pinfunction "I0_1") (pintype "input"))
    )
    (net (code "102") (name "Net-(IC14-D5)") (class "Default")
      (node (ref "IC14") (pin "15") (pinfunction "D5_15") (pintype "tri_state"))
      (node (ref "IC23") (pin "4") (pinfunction "I0_4") (pintype "input"))
    )
    (net (code "103") (name "Net-(IC14-D6)") (class "Default")
      (node (ref "IC14") (pin "16") (pinfunction "D6_16") (pintype "tri_state"))
      (node (ref "IC23") (pin "9") (pinfunction "I0_9") (pintype "input"))
    )
    (net (code "104") (name "Net-(IC14-D7)") (class "Default")
      (node (ref "IC14") (pin "17") (pinfunction "D7_17") (pintype "tri_state"))
      (node (ref "IC23") (pin "12") (pinfunction "I0_12") (pintype "input"))
    )
    (net (code "105") (name "Net-(IC15-D0)") (class "Default")
      (node (ref "IC15") (pin "9") (pinfunction "D0_9") (pintype "tri_state"))
      (node (ref "IC24") (pin "1") (pinfunction "I0_1") (pintype "input"))
    )
    (net (code "106") (name "Net-(IC15-D2)") (class "Default")
      (node (ref "IC15") (pin "11") (pinfunction "D2_11") (pintype "tri_state"))
      (node (ref "IC24") (pin "4") (pinfunction "I0_4") (pintype "input"))
    )
    (net (code "107") (name "Net-(IC15-D3)") (class "Default")
      (node (ref "IC15") (pin "13") (pinfunction "D3_13") (pintype "tri_state"))
      (node (ref "IC24") (pin "9") (pinfunction "I0_9") (pintype "input"))
    )
    (net (code "108") (name "Net-(IC15-D4)") (class "Default")
      (node (ref "IC15") (pin "14") (pinfunction "D4_14") (pintype "tri_state"))
      (node (ref "IC24") (pin "12") (pinfunction "I0_12") (pintype "input"))
    )
    (net (code "109") (name "Net-(IC25A-CLK)") (class "Default")
      (node (ref "IC25") (pin "7") (pinfunction "CLK_7") (pintype "input"))
      (node (ref "IC26") (pin "8") (pinfunction "O_8") (pintype "output"))
      (node (ref "IC28") (pin "11") (pinfunction "CLK_11") (pintype "input"))
    )
    (net (code "110") (name "Net-(IC26A-I1)") (class "Default")
      (node (ref "IC26") (pin "2") (pinfunction "I1_2") (pintype "input"))
      (node (ref "IC27") (pin "2") (pinfunction "Q0_2") (pintype "output"))
    )
    (net (code "111") (name "Net-(IC26B-O)") (class "Default")
      (node (ref "IC26") (pin "6") (pinfunction "O_6") (pintype "output"))
      (node (ref "IC27") (pin "11") (pinfunction "R2_11") (pintype "input"))
      (node (ref "IC27") (pin "3") (pinfunction "R0_3") (pintype "input"))
      (node (ref "IC27") (pin "7") (pinfunction "R1_7") (pintype "input"))
    )
    (net (code "112") (name "Net-(IC27A-Q1)") (class "Default")
      (node (ref "IC27") (pin "9") (pinfunction "Q1_9") (pintype "output"))
      (node (ref "IC30") (pin "1") (pinfunction "OE_1") (pintype "input"))
      (node (ref "IC30") (pin "10") (pinfunction "OE_10") (pintype "input"))
      (node (ref "IC30") (pin "13") (pinfunction "OE_13") (pintype "input"))
      (node (ref "IC30") (pin "4") (pinfunction "OE_4") (pintype "input"))
    )
    (net (code "113") (name "Net-(IC27A-Q2)") (class "Default")
      (node (ref "IC27") (pin "10") (pinfunction "Q2_10") (pintype "output"))
      (node (ref "IC31") (pin "1") (pinfunction "I_1") (pintype "input"))
    )
    (net (code "114") (name "Net-(IC28A-OC)") (class "Default")
      (node (ref "IC25") (pin "1") (pinfunction "DOD_1") (pintype "input"))
      (node (ref "IC25") (pin "2") (pinfunction "DOD_2") (pintype "input"))
      (node (ref "IC28") (pin "1") (pinfunction "OC_1") (pintype "input"))
      (node (ref "IC31") (pin "2") (pinfunction "O_2") (pintype "output"))
    )
    (net (code "115") (name "Net-(IC32A-A1)") (class "Default")
      (node (ref "IC32") (pin "2") (pinfunction "A1_2") (pintype "bidirectional"))
      (node (ref "IC35") (pin "2") (pinfunction "A1_2") (pintype "bidirectional"))
      (node (ref "V1") (pin "3") (pinfunction "QA_3") (pintype "output"))
    )
    (net (code "116") (name "Net-(IC32A-A2)") (class "Default")
      (node (ref "IC32") (pin "3") (pinfunction "A2_3") (pintype "bidirectional"))
      (node (ref "IC35") (pin "3") (pinfunction "A2_3") (pintype "bidirectional"))
      (node (ref "V1") (pin "2") (pinfunction "QB_2") (pintype "output"))
    )
    (net (code "117") (name "Net-(IC32A-A3)") (class "Default")
      (node (ref "IC32") (pin "4") (pinfunction "A3_4") (pintype "bidirectional"))
      (node (ref "IC35") (pin "4") (pinfunction "A3_4") (pintype "bidirectional"))
      (node (ref "V1") (pin "6") (pinfunction "QC_6") (pintype "output"))
    )
    (net (code "118") (name "Net-(IC32A-A4)") (class "Default")
      (node (ref "IC32") (pin "5") (pinfunction "A4_5") (pintype "bidirectional"))
      (node (ref "IC35") (pin "5") (pinfunction "A4_5") (pintype "bidirectional"))
      (node (ref "V1") (pin "7") (pinfunction "QD_7") (pintype "output"))
    )
    (net (code "119") (name "Net-(IC32A-A5)") (class "Default")
      (node (ref "IC32") (pin "6") (pinfunction "A5_6") (pintype "bidirectional"))
      (node (ref "IC35") (pin "6") (pinfunction "A5_6") (pintype "bidirectional"))
      (node (ref "V2") (pin "3") (pinfunction "QA_3") (pintype "output"))
    )
    (net (code "120") (name "Net-(IC32A-A6)") (class "Default")
      (node (ref "IC32") (pin "7") (pinfunction "A6_7") (pintype "bidirectional"))
      (node (ref "IC35") (pin "7") (pinfunction "A6_7") (pintype "bidirectional"))
      (node (ref "V2") (pin "2") (pinfunction "QB_2") (pintype "output"))
    )
    (net (code "121") (name "Net-(IC32A-A7)") (class "Default")
      (node (ref "IC32") (pin "8") (pinfunction "A7_8") (pintype "bidirectional"))
      (node (ref "IC35") (pin "8") (pinfunction "A7_8") (pintype "bidirectional"))
      (node (ref "V2") (pin "6") (pinfunction "QC_6") (pintype "output"))
    )
    (net (code "122") (name "Net-(IC32A-A8)") (class "Default")
      (node (ref "IC32") (pin "9") (pinfunction "A8_9") (pintype "bidirectional"))
      (node (ref "IC35") (pin "9") (pinfunction "A8_9") (pintype "bidirectional"))
      (node (ref "V2") (pin "7") (pinfunction "QD_7") (pintype "output"))
    )
    (net (code "123") (name "Net-(IC32A-G)") (class "Default")
      (node (ref "IC32") (pin "19") (pinfunction "G_19") (pintype "input"))
      (node (ref "IC33") (pin "19") (pinfunction "G_19") (pintype "input"))
      (node (ref "IC39") (pin "8") (pinfunction "O_8") (pintype "output"))
    )
    (net (code "124") (name "Net-(IC33A-A1)") (class "Default")
      (node (ref "IC33") (pin "2") (pinfunction "A1_2") (pintype "bidirectional"))
      (node (ref "IC36") (pin "2") (pinfunction "A1_2") (pintype "bidirectional"))
      (node (ref "V3") (pin "3") (pinfunction "QA_3") (pintype "output"))
    )
    (net (code "125") (name "Net-(IC33A-A2)") (class "Default")
      (node (ref "IC33") (pin "3") (pinfunction "A2_3") (pintype "bidirectional"))
      (node (ref "IC36") (pin "3") (pinfunction "A2_3") (pintype "bidirectional"))
      (node (ref "V3") (pin "2") (pinfunction "QB_2") (pintype "output"))
    )
    (net (code "126") (name "Net-(IC33A-A3)") (class "Default")
      (node (ref "IC33") (pin "4") (pinfunction "A3_4") (pintype "bidirectional"))
      (node (ref "IC36") (pin "4") (pinfunction "A3_4") (pintype "bidirectional"))
      (node (ref "V3") (pin "6") (pinfunction "QC_6") (pintype "output"))
    )
    (net (code "127") (name "Net-(IC34A-Q0)") (class "Default")
      (node (ref "IC34") (pin "2") (pinfunction "Q0_2") (pintype "output"))
      (node (ref "IC35") (pin "19") (pinfunction "G_19") (pintype "input"))
      (node (ref "IC36") (pin "19") (pinfunction "G_19") (pintype "input"))
      (node (ref "IC39") (pin "5") (pinfunction "I_5") (pintype "input"))
    )
    (net (code "128") (name "Net-(IC34A-Q1)") (class "Default")
      (node (ref "IC34") (pin "9") (pinfunction "Q1_9") (pintype "output"))
      (node (ref "IC39") (pin "9") (pinfunction "I_9") (pintype "input"))
    )
    (net (code "129") (name "Net-(IC34A-R0)") (class "Default")
      (node (ref "IC34") (pin "3") (pinfunction "R0_3") (pintype "input"))
      (node (ref "IC40") (pin "3") (pinfunction "O_3") (pintype "output"))
    )
    (net (code "130") (name "Net-(IC34A-R1)") (class "Default")
      (node (ref "IC34") (pin "7") (pinfunction "R1_7") (pintype "input"))
      (node (ref "IC40") (pin "6") (pinfunction "O_6") (pintype "output"))
    )
    (net (code "131") (name "Net-(IC37A-OC)") (class "Default")
      (node (ref "IC37") (pin "1") (pinfunction "OC_1") (pintype "input"))
      (node (ref "IC38") (pin "1") (pinfunction "DOD_1") (pintype "input"))
      (node (ref "IC38") (pin "2") (pinfunction "DOD_2") (pintype "input"))
      (node (ref "IC39") (pin "6") (pinfunction "O_6") (pintype "output"))
    )
    (net (code "132") (name "Net-(IC39A-O)") (class "Default")
      (node (ref "IC39") (pin "2") (pinfunction "O_2") (pintype "output"))
      (node (ref "V1") (pin "5") (pinfunction "UP_5") (pintype "input"))
    )
    (net (code "133") (name "Net-(IC39B-I)") (class "Default")
      (node (ref "IC39") (pin "3") (pinfunction "I_3") (pintype "input"))
      (node (ref "IC40") (pin "8") (pinfunction "O_8") (pintype "output"))
    )
    (net (code "134") (name "Net-(IC39B-O)") (class "Default")
      (node (ref "IC39") (pin "4") (pinfunction "O_4") (pintype "output"))
      (node (ref "V1") (pin "11") (pinfunction "~{LOAD}_11") (pintype "input"))
      (node (ref "V2") (pin "11") (pinfunction "~{LOAD}_11") (pintype "input"))
      (node (ref "V3") (pin "11") (pinfunction "~{LOAD}_11") (pintype "input"))
    )
    (net (code "135") (name "Net-(IC41A-A0)") (class "Default")
      (node (ref "IC41") (pin "2") (pinfunction "A0_2") (pintype "input"))
      (node (ref "IC42") (pin "2") (pinfunction "Q0_2") (pintype "output"))
      (node (ref "IC46") (pin "5") (pinfunction "I_5") (pintype "input"))
      (node (ref "IC51") (pin "1") (pinfunction "I0_1") (pintype "input"))
    )
    (net (code "136") (name "Net-(IC41A-A1)") (class "Default")
      (node (ref "IC41") (pin "23") (pinfunction "A1_23") (pintype "input"))
      (node (ref "IC42") (pin "10") (pinfunction "Q1_10") (pintype "output"))
      (node (ref "IC51") (pin "5") (pinfunction "I1_5") (pintype "input"))
    )
    (net (code "137") (name "Net-(IC41A-A2)") (class "Default")
      (node (ref "IC41") (pin "21") (pinfunction "A2_21") (pintype "input"))
      (node (ref "IC42") (pin "11") (pinfunction "Q2_11") (pintype "output"))
      (node (ref "IC46") (pin "9") (pinfunction "I_9") (pintype "input"))
      (node (ref "IC51") (pin "2") (pinfunction "I1_2") (pintype "input"))
    )
    (net (code "138") (name "Net-(IC41A-A3)") (class "Default")
      (node (ref "IC41") (pin "19") (pinfunction "A3_19") (pintype "input"))
      (node (ref "IC42") (pin "1") (pinfunction "Q3_1") (pintype "output"))
      (node (ref "IC51") (pin "4") (pinfunction "I0_4") (pintype "input"))
    )
    (net (code "139") (name "Net-(IC41A-A=B)") (class "Default")
      (node (ref "IC41") (pin "14") (pinfunction "A=B_14") (pintype "output"))
      (node (ref "IC46") (pin "1") (pinfunction "I_1") (pintype "input"))
      (node (ref "IC47") (pin "4") (pinfunction "A3_4") (pintype "bidirectional"))
    )
    (net (code "140") (name "Net-(IC41A-B0)") (class "Default")
      (node (ref "IC41") (pin "1") (pinfunction "B0_1") (pintype "input"))
      (node (ref "IC43") (pin "2") (pinfunction "Q0_2") (pintype "output"))
    )
    (net (code "141") (name "Net-(IC41A-B1)") (class "Default")
      (node (ref "IC41") (pin "22") (pinfunction "B1_22") (pintype "input"))
      (node (ref "IC43") (pin "10") (pinfunction "Q1_10") (pintype "output"))
    )
    (net (code "142") (name "Net-(IC41A-B2)") (class "Default")
      (node (ref "IC41") (pin "20") (pinfunction "B2_20") (pintype "input"))
      (node (ref "IC43") (pin "11") (pinfunction "Q2_11") (pintype "output"))
    )
    (net (code "143") (name "Net-(IC41A-B3)") (class "Default")
      (node (ref "IC41") (pin "18") (pinfunction "B3_18") (pintype "input"))
      (node (ref "IC43") (pin "1") (pinfunction "Q3_1") (pintype "output"))
    )
    (net (code "144") (name "Net-(IC41A-CN)") (class "Default")
      (node (ref "IC41") (pin "7") (pinfunction "CN_7") (pintype "input"))
      (node (ref "IC45") (pin "3") (pinfunction "O_3") (pintype "output"))
    )
    (net (code "145") (name "Net-(IC41A-CN+4)") (class "Default")
      (node (ref "IC41") (pin "16") (pinfunction "CN+4_16") (pintype "output"))
      (node (ref "IC46") (pin "3") (pinfunction "I_3") (pintype "input"))
      (node (ref "IC52") (pin "5") (pinfunction "I1_5") (pintype "input"))
    )
    (net (code "146") (name "Net-(IC41A-F0)") (class "Default")
      (node (ref "IC41") (pin "9") (pinfunction "F0_9") (pintype "output"))
      (node (ref "IC50") (pin "14") (pinfunction "D0_14") (pintype "input"))
    )
    (net (code "147") (name "Net-(IC41A-F1)") (class "Default")
      (node (ref "IC41") (pin "10") (pinfunction "F1_10") (pintype "output"))
      (node (ref "IC50") (pin "13") (pinfunction "D1_13") (pintype "input"))
    )
    (net (code "148") (name "Net-(IC41A-F2)") (class "Default")
      (node (ref "IC41") (pin "11") (pinfunction "F2_11") (pintype "output"))
      (node (ref "IC50") (pin "12") (pinfunction "D2_12") (pintype "input"))
    )
    (net (code "149") (name "Net-(IC41A-F3)") (class "Default")
      (node (ref "IC41") (pin "13") (pinfunction "F3_13") (pintype "output"))
      (node (ref "IC50") (pin "11") (pinfunction "D3_11") (pintype "input"))
    )
    (net (code "150") (name "Net-(IC41A-M)") (class "Default")
      (node (ref "IC41") (pin "8") (pinfunction "M_8") (pintype "input"))
      (node (ref "IC48") (pin "10") (pinfunction "Q2_10") (pintype "output"))
    )
    (net (code "151") (name "Net-(IC41A-S0)") (class "Default")
      (node (ref "IC41") (pin "6") (pinfunction "S0_6") (pintype "input"))
      (node (ref "IC44") (pin "10") (pinfunction "I1_10") (pintype "input"))
      (node (ref "IC44") (pin "13") (pinfunction "I1_13") (pintype "input"))
      (node (ref "IC44") (pin "5") (pinfunction "I1_5") (pintype "input"))
      (node (ref "IC45") (pin "2") (pinfunction "I1_2") (pintype "input"))
      (node (ref "IC48") (pin "1") (pinfunction "Q3_1") (pintype "output"))
    )
    (net (code "152") (name "Net-(IC41A-S1)") (class "Default")
      (node (ref "IC41") (pin "5") (pinfunction "S1_5") (pintype "input"))
      (node (ref "IC44") (pin "11") (pinfunction "O_11") (pintype "output"))
    )
    (net (code "153") (name "Net-(IC41A-S2)") (class "Default")
      (node (ref "IC41") (pin "4") (pinfunction "S2_4") (pintype "input"))
      (node (ref "IC44") (pin "8") (pinfunction "O_8") (pintype "output"))
    )
    (net (code "154") (name "Net-(IC41A-S3)") (class "Default")
      (node (ref "IC41") (pin "3") (pinfunction "S3_3") (pintype "input"))
      (node (ref "IC44") (pin "6") (pinfunction "O_6") (pintype "output"))
    )
    (net (code "155") (name "Net-(IC44A-I0)") (class "Default")
      (node (ref "IC44") (pin "1") (pinfunction "I0_1") (pintype "input"))
      (node (ref "IC44") (pin "9") (pinfunction "I0_9") (pintype "input"))
      (node (ref "IC45") (pin "1") (pinfunction "I0_1") (pintype "input"))
      (node (ref "IC48") (pin "2") (pinfunction "Q0_2") (pintype "output"))
    )
    (net (code "156") (name "Net-(IC44A-I1)") (class "Default")
      (node (ref "IC44") (pin "2") (pinfunction "I1_2") (pintype "input"))
      (node (ref "IC44") (pin "4") (pinfunction "I0_4") (pintype "input"))
      (node (ref "IC48") (pin "9") (pinfunction "Q1_9") (pintype "output"))
    )
    (net (code "157") (name "Net-(IC44A-O)") (class "Default")
      (node (ref "IC44") (pin "12") (pinfunction "I0_12") (pintype "input"))
      (node (ref "IC44") (pin "3") (pinfunction "O_3") (pintype "output"))
    )
    (net (code "158") (name "Net-(IC45B-O)") (class "Default")
      (node (ref "IC45") (pin "6") (pinfunction "O_6") (pintype "output"))
      (node (ref "IC48") (pin "11") (pinfunction "R2_11") (pintype "input"))
      (node (ref "IC48") (pin "15") (pinfunction "R3_15") (pintype "input"))
      (node (ref "IC48") (pin "3") (pinfunction "R0_3") (pintype "input"))
      (node (ref "IC48") (pin "7") (pinfunction "R1_7") (pintype "input"))
      (node (ref "IC49") (pin "3") (pinfunction "R0_3") (pintype "input"))
      (node (ref "IC49") (pin "7") (pinfunction "R1_7") (pintype "input"))
    )
    (net (code "159") (name "Net-(IC46A-O)") (class "Default")
      (node (ref "IC46") (pin "2") (pinfunction "O_2") (pintype "output"))
      (node (ref "IC52") (pin "4") (pinfunction "I0_4") (pintype "input"))
      (node (ref "IC52") (pin "9") (pinfunction "I0_9") (pintype "input"))
    )
    (net (code "160") (name "Net-(IC46B-O)") (class "Default")
      (node (ref "IC46") (pin "4") (pinfunction "O_4") (pintype "output"))
      (node (ref "IC52") (pin "10") (pinfunction "I1_10") (pintype "input"))
    )
    (net (code "161") (name "Net-(IC46C-O)") (class "Default")
      (node (ref "IC46") (pin "6") (pinfunction "O_6") (pintype "output"))
      (node (ref "IC51") (pin "12") (pinfunction "I0_12") (pintype "input"))
    )
    (net (code "162") (name "Net-(IC46D-O)") (class "Default")
      (node (ref "IC46") (pin "8") (pinfunction "O_8") (pintype "output"))
      (node (ref "IC51") (pin "13") (pinfunction "I1_13") (pintype "input"))
    )
    (net (code "163") (name "Net-(IC46E-I)") (class "Default")
      (node (ref "IC46") (pin "11") (pinfunction "I_11") (pintype "input"))
      (node (ref "IC49") (pin "2") (pinfunction "Q0_2") (pintype "output"))
    )
    (net (code "164") (name "Net-(IC46E-O)") (class "Default")
      (node (ref "IC46") (pin "10") (pinfunction "O_10") (pintype "output"))
      (node (ref "IC47") (pin "19") (pinfunction "G_19") (pintype "input"))
    )
    (net (code "165") (name "Net-(IC46F-I)") (class "Default")
      (node (ref "IC46") (pin "13") (pinfunction "I_13") (pintype "input"))
      (node (ref "IC49") (pin "9") (pinfunction "Q1_9") (pintype "output"))
    )
    (net (code "166") (name "Net-(IC46F-O)") (class "Default")
      (node (ref "IC46") (pin "12") (pinfunction "O_12") (pintype "output"))
      (node (ref "IC50") (pin "1") (pinfunction "DOD_1") (pintype "input"))
      (node (ref "IC50") (pin "2") (pinfunction "DOD_2") (pintype "input"))
    )
    (net (code "167") (name "Net-(IC47A-A1)") (class "Default")
      (node (ref "IC47") (pin "2") (pinfunction "A1_2") (pintype "bidirectional"))
      (node (ref "IC51") (pin "8") (pinfunction "O_8") (pintype "output"))
    )
    (net (code "168") (name "Net-(IC47A-A2)") (class "Default")
      (node (ref "IC47") (pin "3") (pinfunction "A2_3") (pintype "bidirectional"))
      (node (ref "IC52") (pin "3") (pinfunction "O_3") (pintype "output"))
    )
    (net (code "169") (name "Net-(IC47A-A4)") (class "Default")
      (node (ref "IC47") (pin "5") (pinfunction "A4_5") (pintype "bidirectional"))
      (node (ref "IC52") (pin "6") (pinfunction "O_6") (pintype "output"))
    )
    (net (code "170") (name "Net-(IC47A-A5)") (class "Default")
      (node (ref "IC47") (pin "6") (pinfunction "A5_6") (pintype "bidirectional"))
      (node (ref "IC52") (pin "8") (pinfunction "O_8") (pintype "output"))
    )
    (net (code "171") (name "Net-(IC51A-O)") (class "Default")
      (node (ref "IC51") (pin "3") (pinfunction "O_3") (pintype "output"))
      (node (ref "IC51") (pin "9") (pinfunction "I0_9") (pintype "input"))
    )
    (net (code "172") (name "Net-(IC51B-O)") (class "Default")
      (node (ref "IC51") (pin "10") (pinfunction "I1_10") (pintype "input"))
      (node (ref "IC51") (pin "6") (pinfunction "O_6") (pintype "output"))
      (node (ref "IC52") (pin "1") (pinfunction "I0_1") (pintype "input"))
    )
    (net (code "173") (name "Net-(IC51D-O)") (class "Default")
      (node (ref "IC51") (pin "11") (pinfunction "O_11") (pintype "output"))
      (node (ref "IC52") (pin "2") (pinfunction "I1_2") (pintype "input"))
    )
    (net (code "174") (name "Net-(IC53A-I0)") (class "Default")
      (node (ref "IC53") (pin "1") (pinfunction "I0_1") (pintype "input"))
      (node (ref "IC58") (pin "2") (pinfunction "A1_2") (pintype "bidirectional"))
      (node (ref "IC60") (pin "2") (pinfunction "1Q_2") (pintype "tri_state"))
    )
    (net (code "175") (name "Net-(IC53A-O)") (class "Default")
      (node (ref "IC53") (pin "3") (pinfunction "O_3") (pintype "output"))
      (node (ref "IC55") (pin "4") (pinfunction "I0_4") (pintype "input"))
    )
    (net (code "176") (name "Net-(IC53B-I0)") (class "Default")
      (node (ref "IC53") (pin "4") (pinfunction "I0_4") (pintype "input"))
      (node (ref "IC58") (pin "3") (pinfunction "A2_3") (pintype "bidirectional"))
      (node (ref "IC60") (pin "5") (pinfunction "2Q_5") (pintype "tri_state"))
    )
    (net (code "177") (name "Net-(IC53B-O)") (class "Default")
      (node (ref "IC53") (pin "6") (pinfunction "O_6") (pintype "output"))
      (node (ref "IC55") (pin "5") (pinfunction "I1_5") (pintype "input"))
    )
    (net (code "178") (name "Net-(IC53C-I0)") (class "Default")
      (node (ref "IC53") (pin "9") (pinfunction "I0_9") (pintype "input"))
      (node (ref "IC58") (pin "4") (pinfunction "A3_4") (pintype "bidirectional"))
      (node (ref "IC60") (pin "6") (pinfunction "3Q_6") (pintype "tri_state"))
    )
    (net (code "179") (name "Net-(IC53C-O)") (class "Default")
      (node (ref "IC53") (pin "8") (pinfunction "O_8") (pintype "output"))
      (node (ref "IC55") (pin "9") (pinfunction "I0_9") (pintype "input"))
    )
    (net (code "180") (name "Net-(IC53D-I0)") (class "Default")
      (node (ref "IC53") (pin "12") (pinfunction "I0_12") (pintype "input"))
      (node (ref "IC58") (pin "5") (pinfunction "A4_5") (pintype "bidirectional"))
      (node (ref "IC60") (pin "9") (pinfunction "4Q_9") (pintype "tri_state"))
    )
    (net (code "181") (name "Net-(IC53D-O)") (class "Default")
      (node (ref "IC53") (pin "11") (pinfunction "O_11") (pintype "output"))
      (node (ref "IC55") (pin "10") (pinfunction "I1_10") (pintype "input"))
    )
    (net (code "182") (name "Net-(IC54A-I0)") (class "Default")
      (node (ref "IC54") (pin "1") (pinfunction "I0_1") (pintype "input"))
      (node (ref "IC58") (pin "6") (pinfunction "A5_6") (pintype "bidirectional"))
      (node (ref "IC60") (pin "12") (pinfunction "5Q_12") (pintype "tri_state"))
    )
    (net (code "183") (name "Net-(IC54A-O)") (class "Default")
      (node (ref "IC54") (pin "3") (pinfunction "O_3") (pintype "output"))
      (node (ref "IC59") (pin "2") (pinfunction "I1_2") (pintype "input"))
    )
    (net (code "184") (name "Net-(IC55A-O)") (class "Default")
      (node (ref "IC55") (pin "3") (pinfunction "O_3") (pintype "output"))
      (node (ref "IC56") (pin "3") (pinfunction "R0_3") (pintype "input"))
    )
    (net (code "185") (name "Net-(IC55B-O)") (class "Default")
      (node (ref "IC55") (pin "12") (pinfunction "I0_12") (pintype "input"))
      (node (ref "IC55") (pin "6") (pinfunction "O_6") (pintype "output"))
    )
    (net (code "186") (name "Net-(IC55C-O)") (class "Default")
      (node (ref "IC55") (pin "13") (pinfunction "I1_13") (pintype "input"))
      (node (ref "IC55") (pin "8") (pinfunction "O_8") (pintype "output"))
    )
    (net (code "187") (name "Net-(IC55D-O)") (class "Default")
      (node (ref "IC55") (pin "11") (pinfunction "O_11") (pintype "output"))
      (node (ref "IC59") (pin "1") (pinfunction "I0_1") (pintype "input"))
    )
    (net (code "188") (name "Net-(IC56A-Q0)") (class "Default")
      (node (ref "IC56") (pin "2") (pinfunction "Q0_2") (pintype "output"))
      (node (ref "IC57") (pin "1") (pinfunction "I_1") (pintype "input"))
    )
    (net (code "189") (name "Net-(IC57A-O)") (class "Default")
      (node (ref "IC57") (pin "2") (pinfunction "O_2") (pintype "output"))
      (node (ref "IC58") (pin "19") (pinfunction "G_19") (pintype "input"))
    )
    (net (code "190") (name "Net-(IC61A-Q0)") (class "Default")
      (node (ref "IC61") (pin "2") (pinfunction "Q0_2") (pintype "output"))
      (node (ref "IC68") (pin "1") (pinfunction "I_1") (pintype "input"))
    )
    (net (code "191") (name "Net-(IC61A-Q1)") (class "Default")
      (node (ref "IC61") (pin "9") (pinfunction "Q1_9") (pintype "output"))
      (node (ref "IC68") (pin "3") (pinfunction "I_3") (pintype "input"))
    )
    (net (code "192") (name "Net-(IC61A-Q2)") (class "Default")
      (node (ref "IC61") (pin "10") (pinfunction "Q2_10") (pintype "output"))
      (node (ref "IC68") (pin "5") (pinfunction "I_5") (pintype "input"))
    )
    (net (code "193") (name "Net-(IC61A-Q3)") (class "Default")
      (node (ref "IC61") (pin "1") (pinfunction "Q3_1") (pintype "output"))
      (node (ref "IC68") (pin "9") (pinfunction "I_9") (pintype "input"))
    )
    (net (code "194") (name "Net-(IC61A-R0)") (class "Default")
      (node (ref "IC61") (pin "11") (pinfunction "R2_11") (pintype "input"))
      (node (ref "IC61") (pin "15") (pinfunction "R3_15") (pintype "input"))
      (node (ref "IC61") (pin "3") (pinfunction "R0_3") (pintype "input"))
      (node (ref "IC61") (pin "7") (pinfunction "R1_7") (pintype "input"))
      (node (ref "IC62") (pin "3") (pinfunction "O_3") (pintype "output"))
    )
    (net (code "195") (name "Net-(IC65A-OC)") (class "Default")
      (node (ref "IC65") (pin "1") (pinfunction "OC_1") (pintype "input"))
      (node (ref "IC68") (pin "6") (pinfunction "O_6") (pintype "output"))
    )
    (net (code "196") (name "Net-(IC66A-OC)") (class "Default")
      (node (ref "IC66") (pin "1") (pinfunction "OC_1") (pintype "input"))
      (node (ref "IC67") (pin "1") (pinfunction "DOD_1") (pintype "input"))
      (node (ref "IC67") (pin "2") (pinfunction "DOD_2") (pintype "input"))
      (node (ref "IC68") (pin "8") (pinfunction "O_8") (pintype "output"))
    )
    (net (code "197") (name "Net-(IC68A-O)") (class "Default")
      (node (ref "IC63") (pin "1") (pinfunction "DOD_1") (pintype "input"))
      (node (ref "IC63") (pin "2") (pinfunction "DOD_2") (pintype "input"))
      (node (ref "IC68") (pin "2") (pinfunction "O_2") (pintype "output"))
    )
    (net (code "198") (name "Net-(IC68B-O)") (class "Default")
      (node (ref "IC64") (pin "1") (pinfunction "DOD_1") (pintype "input"))
      (node (ref "IC64") (pin "2") (pinfunction "DOD_2") (pintype "input"))
      (node (ref "IC68") (pin "4") (pinfunction "O_4") (pintype "output"))
    )
    (net (code "199") (name "Net-(V1C-~{CO})") (class "Default")
      (node (ref "V1") (pin "12") (pinfunction "~{CO}_12") (pintype "output"))
      (node (ref "V2") (pin "5") (pinfunction "UP_5") (pintype "input"))
    )
    (net (code "200") (name "Net-(V2C-~{CO})") (class "Default")
      (node (ref "V2") (pin "12") (pinfunction "~{CO}_12") (pintype "output"))
      (node (ref "V3") (pin "5") (pinfunction "UP_5") (pintype "input"))
    )
    (net (code "201") (name "OP0") (class "Default")
      (node (ref "IC29") (pin "3") (pinfunction "1D_3") (pintype "input"))
      (node (ref "JP2") (pin "3") (pinfunction "3_3") (pintype "passive"))
    )
    (net (code "202") (name "OP1") (class "Default")
      (node (ref "IC29") (pin "4") (pinfunction "2D_4") (pintype "input"))
      (node (ref "JP2") (pin "4") (pinfunction "4_4") (pintype "passive"))
    )
    (net (code "203") (name "OP2") (class "Default")
      (node (ref "IC29") (pin "7") (pinfunction "3D_7") (pintype "input"))
      (node (ref "JP2") (pin "5") (pinfunction "5_5") (pintype "passive"))
    )
    (net (code "204") (name "OP3") (class "Default")
      (node (ref "IC29") (pin "8") (pinfunction "4D_8") (pintype "input"))
      (node (ref "JP2") (pin "6") (pinfunction "6_6") (pintype "passive"))
    )
    (net (code "205") (name "OP4") (class "Default")
      (node (ref "IC29") (pin "13") (pinfunction "5D_13") (pintype "input"))
      (node (ref "JP2") (pin "7") (pinfunction "7_7") (pintype "passive"))
    )
    (net (code "206") (name "OPCOUNTER0") (class "Default")
      (node (ref "IC11") (pin "8") (pinfunction "A0_8") (pintype "input"))
      (node (ref "IC12") (pin "8") (pinfunction "A0_8") (pintype "input"))
      (node (ref "IC13") (pin "8") (pinfunction "A0_8") (pintype "input"))
      (node (ref "IC14") (pin "8") (pinfunction "A0_8") (pintype "input"))
      (node (ref "IC15") (pin "8") (pinfunction "A0_8") (pintype "input"))
      (node (ref "IC6") (pin "9") (pinfunction "Q1_9") (pintype "output"))
    )
    (net (code "207") (name "OPCOUNTER1") (class "Default")
      (node (ref "IC11") (pin "7") (pinfunction "A1_7") (pintype "input"))
      (node (ref "IC12") (pin "7") (pinfunction "A1_7") (pintype "input"))
      (node (ref "IC13") (pin "7") (pinfunction "A1_7") (pintype "input"))
      (node (ref "IC14") (pin "7") (pinfunction "A1_7") (pintype "input"))
      (node (ref "IC15") (pin "7") (pinfunction "A1_7") (pintype "input"))
      (node (ref "IC6") (pin "7") (pinfunction "Q2_7") (pintype "output"))
    )
    (net (code "208") (name "OPCOUNTER2") (class "Default")
      (node (ref "IC11") (pin "6") (pinfunction "A2_6") (pintype "input"))
      (node (ref "IC12") (pin "6") (pinfunction "A2_6") (pintype "input"))
      (node (ref "IC13") (pin "6") (pinfunction "A2_6") (pintype "input"))
      (node (ref "IC14") (pin "6") (pinfunction "A2_6") (pintype "input"))
      (node (ref "IC15") (pin "6") (pinfunction "A2_6") (pintype "input"))
      (node (ref "IC6") (pin "6") (pinfunction "Q3_6") (pintype "output"))
    )
    (net (code "209") (name "OPCOUNTER3") (class "Default")
      (node (ref "IC11") (pin "5") (pinfunction "A3_5") (pintype "input"))
      (node (ref "IC12") (pin "5") (pinfunction "A3_5") (pintype "input"))
      (node (ref "IC13") (pin "5") (pinfunction "A3_5") (pintype "input"))
      (node (ref "IC14") (pin "5") (pinfunction "A3_5") (pintype "input"))
      (node (ref "IC15") (pin "5") (pinfunction "A3_5") (pintype "input"))
      (node (ref "IC6") (pin "5") (pinfunction "Q4_5") (pintype "output"))
    )
    (net (code "210") (name "OPCOUNTER4") (class "Default")
      (node (ref "IC11") (pin "4") (pinfunction "A4_4") (pintype "input"))
      (node (ref "IC12") (pin "4") (pinfunction "A4_4") (pintype "input"))
      (node (ref "IC13") (pin "4") (pinfunction "A4_4") (pintype "input"))
      (node (ref "IC14") (pin "4") (pinfunction "A4_4") (pintype "input"))
      (node (ref "IC15") (pin "4") (pinfunction "A4_4") (pintype "input"))
      (node (ref "IC6") (pin "3") (pinfunction "Q5_3") (pintype "output"))
    )
    (net (code "211") (name "OPERATIONDONE") (class "Default")
      (node (ref "IC3") (pin "2") (pinfunction "I1_2") (pintype "input"))
      (node (ref "IC8") (pin "5") (pinfunction "I1_5") (pintype "input"))
      (node (ref "IC9") (pin "5") (pinfunction "Q_5") (pintype "output"))
    )
    (net (code "212") (name "OPREGISTER0") (class "Default")
      (node (ref "IC11") (pin "3") (pinfunction "A5_3") (pintype "input"))
      (node (ref "IC12") (pin "3") (pinfunction "A5_3") (pintype "input"))
      (node (ref "IC13") (pin "3") (pinfunction "A5_3") (pintype "input"))
      (node (ref "IC14") (pin "3") (pinfunction "A5_3") (pintype "input"))
      (node (ref "IC15") (pin "3") (pinfunction "A5_3") (pintype "input"))
      (node (ref "IC29") (pin "2") (pinfunction "1Q_2") (pintype "tri_state"))
    )
    (net (code "213") (name "OPREGISTER1") (class "Default")
      (node (ref "IC11") (pin "2") (pinfunction "A6_2") (pintype "input"))
      (node (ref "IC12") (pin "2") (pinfunction "A6_2") (pintype "input"))
      (node (ref "IC13") (pin "2") (pinfunction "A6_2") (pintype "input"))
      (node (ref "IC14") (pin "2") (pinfunction "A6_2") (pintype "input"))
      (node (ref "IC15") (pin "2") (pinfunction "A6_2") (pintype "input"))
      (node (ref "IC29") (pin "5") (pinfunction "2Q_5") (pintype "tri_state"))
    )
    (net (code "214") (name "OPREGISTER2") (class "Default")
      (node (ref "IC11") (pin "1") (pinfunction "A7_1") (pintype "input"))
      (node (ref "IC12") (pin "1") (pinfunction "A7_1") (pintype "input"))
      (node (ref "IC13") (pin "1") (pinfunction "A7_1") (pintype "input"))
      (node (ref "IC14") (pin "1") (pinfunction "A7_1") (pintype "input"))
      (node (ref "IC15") (pin "1") (pinfunction "A7_1") (pintype "input"))
      (node (ref "IC29") (pin "6") (pinfunction "3Q_6") (pintype "tri_state"))
    )
    (net (code "215") (name "OPREGISTER3") (class "Default")
      (node (ref "IC11") (pin "23") (pinfunction "A8_23") (pintype "input"))
      (node (ref "IC12") (pin "23") (pinfunction "A8_23") (pintype "input"))
      (node (ref "IC13") (pin "23") (pinfunction "A8_23") (pintype "input"))
      (node (ref "IC14") (pin "23") (pinfunction "A8_23") (pintype "input"))
      (node (ref "IC15") (pin "23") (pinfunction "A8_23") (pintype "input"))
      (node (ref "IC29") (pin "9") (pinfunction "4Q_9") (pintype "tri_state"))
    )
    (net (code "216") (name "OPREGISTER4") (class "Default")
      (node (ref "IC11") (pin "22") (pinfunction "A9_22") (pintype "input"))
      (node (ref "IC12") (pin "22") (pinfunction "A9_22") (pintype "input"))
      (node (ref "IC13") (pin "22") (pinfunction "A9_22") (pintype "input"))
      (node (ref "IC14") (pin "22") (pinfunction "A9_22") (pintype "input"))
      (node (ref "IC15") (pin "22") (pinfunction "A9_22") (pintype "input"))
      (node (ref "IC29") (pin "12") (pinfunction "5Q_12") (pintype "tri_state"))
    )
    (net (code "217") (name "OVERFLOW") (class "Default")
      (node (ref "IC18") (pin "6") (pinfunction "O_6") (pintype "output"))
      (node (ref "IC53") (pin "5") (pinfunction "I1_5") (pintype "input"))
    )
    (net (code "218") (name "PC1ACTIVE") (class "Default")
      (node (ref "IC23") (pin "6") (pinfunction "O_6") (pintype "output"))
      (node (ref "IC40") (pin "2") (pinfunction "I1_2") (pintype "input"))
    )
    (net (code "219") (name "PC1FLAGLATCH") (class "Default")
      (node (ref "IC40") (pin "9") (pinfunction "I0_9") (pintype "input"))
      (node (ref "IC59") (pin "3") (pinfunction "O_3") (pintype "output"))
    )
    (net (code "220") (name "PC1LATCH") (class "Default")
      (node (ref "IC23") (pin "11") (pinfunction "O_11") (pintype "output"))
      (node (ref "IC40") (pin "10") (pinfunction "I1_10") (pintype "input"))
    )
    (net (code "221") (name "PC1TODATABUS") (class "Default")
      (node (ref "IC22") (pin "11") (pinfunction "O_11") (pintype "output"))
      (node (ref "IC34") (pin "6") (pinfunction "S1_6") (pintype "input"))
    )
    (net (code "222") (name "PC2ACTIVE") (class "Default")
      (node (ref "IC23") (pin "3") (pinfunction "O_3") (pintype "output"))
      (node (ref "IC34") (pin "4") (pinfunction "S0_4") (pintype "input"))
    )
    (net (code "223") (name "PC2LATCH") (class "Default")
      (node (ref "IC23") (pin "8") (pinfunction "O_8") (pintype "output"))
      (node (ref "IC37") (pin "11") (pinfunction "CLK_11") (pintype "input"))
      (node (ref "IC38") (pin "7") (pinfunction "CLK_7") (pintype "input"))
    )
    (net (code "224") (name "PCINC") (class "Default")
      (node (ref "IC1") (pin "10") (pinfunction "Q4_10") (pintype "output"))
      (node (ref "IC39") (pin "1") (pinfunction "I_1") (pintype "input"))
    )
    (net (code "225") (name "PCJSRLATCH") (class "Default")
      (node (ref "IC20") (pin "6") (pinfunction "O_6") (pintype "output"))
      (node (ref "IC66") (pin "11") (pinfunction "CLK_11") (pintype "input"))
      (node (ref "IC67") (pin "7") (pinfunction "CLK_7") (pintype "input"))
    )
    (net (code "226") (name "PCJSROUTPUT") (class "Default")
      (node (ref "IC20") (pin "3") (pinfunction "O_3") (pintype "output"))
      (node (ref "IC61") (pin "14") (pinfunction "S3_14") (pintype "input"))
    )
    (net (code "227") (name "RAMREAD") (class "Default")
      (node (ref "IC26") (pin "3") (pinfunction "O_3") (pintype "output"))
      (node (ref "JP2") (pin "1") (pinfunction "1_1") (pintype "passive"))
    )
    (net (code "228") (name "RAMWRITE") (class "Default")
      (node (ref "IC24") (pin "8") (pinfunction "O_8") (pintype "output"))
      (node (ref "JP2") (pin "2") (pinfunction "2_2") (pintype "passive"))
    )
    (net (code "229") (name "START") (class "Default")
      (node (ref "IC2") (pin "6") (pinfunction "S1_6") (pintype "input"))
      (node (ref "JP1") (pin "1") (pinfunction "1_1") (pintype "passive"))
    )
    (net (code "230") (name "STOP") (class "Default")
      (node (ref "IC24") (pin "3") (pinfunction "O_3") (pintype "output"))
      (node (ref "IC3") (pin "12") (pinfunction "I0_12") (pintype "input"))
    )
    (net (code "231") (name "SUP") (class "Default")
      (node (ref "IC1") (pin "13") (pinfunction "ENA_13") (pintype "input"))
      (node (ref "IC11") (pin "12") (pinfunction "GND_12") (pintype "power_in"))
      (node (ref "IC11") (pin "18") (pinfunction "~{CE}_18") (pintype "input"))
      (node (ref "IC11") (pin "19") (pinfunction "A10_19") (pintype "input"))
      (node (ref "IC11") (pin "20") (pinfunction "~{OE}_20") (pintype "input"))
      (node (ref "IC12") (pin "12") (pinfunction "GND_12") (pintype "power_in"))
      (node (ref "IC12") (pin "18") (pinfunction "~{CE}_18") (pintype "input"))
      (node (ref "IC12") (pin "19") (pinfunction "A10_19") (pintype "input"))
      (node (ref "IC12") (pin "20") (pinfunction "~{OE}_20") (pintype "input"))
      (node (ref "IC13") (pin "12") (pinfunction "GND_12") (pintype "power_in"))
      (node (ref "IC13") (pin "18") (pinfunction "~{CE}_18") (pintype "input"))
      (node (ref "IC13") (pin "19") (pinfunction "A10_19") (pintype "input"))
      (node (ref "IC13") (pin "20") (pinfunction "~{OE}_20") (pintype "input"))
      (node (ref "IC14") (pin "12") (pinfunction "GND_12") (pintype "power_in"))
      (node (ref "IC14") (pin "18") (pinfunction "~{CE}_18") (pintype "input"))
      (node (ref "IC14") (pin "19") (pinfunction "A10_19") (pintype "input"))
      (node (ref "IC14") (pin "20") (pinfunction "~{OE}_20") (pintype "input"))
      (node (ref "IC15") (pin "12") (pinfunction "GND_12") (pintype "power_in"))
      (node (ref "IC15") (pin "18") (pinfunction "~{CE}_18") (pintype "input"))
      (node (ref "IC15") (pin "19") (pinfunction "A10_19") (pintype "input"))
      (node (ref "IC15") (pin "20") (pinfunction "~{OE}_20") (pintype "input"))
      (node (ref "IC25") (pin "10") (pinfunction "DID_10") (pintype "input"))
      (node (ref "IC25") (pin "15") (pinfunction "CLR_15") (pintype "input"))
      (node (ref "IC25") (pin "9") (pinfunction "DID_9") (pintype "input"))
      (node (ref "IC29") (pin "1") (pinfunction "OC_1") (pintype "input"))
      (node (ref "IC38") (pin "10") (pinfunction "DID_10") (pintype "input"))
      (node (ref "IC38") (pin "15") (pinfunction "CLR_15") (pintype "input"))
      (node (ref "IC38") (pin "9") (pinfunction "DID_9") (pintype "input"))
      (node (ref "IC50") (pin "10") (pinfunction "DID_10") (pintype "input"))
      (node (ref "IC50") (pin "15") (pinfunction "CLR_15") (pintype "input"))
      (node (ref "IC50") (pin "9") (pinfunction "DID_9") (pintype "input"))
      (node (ref "IC60") (pin "1") (pinfunction "OC_1") (pintype "input"))
      (node (ref "IC63") (pin "10") (pinfunction "DID_10") (pintype "input"))
      (node (ref "IC63") (pin "15") (pinfunction "CLR_15") (pintype "input"))
      (node (ref "IC63") (pin "9") (pinfunction "DID_9") (pintype "input"))
      (node (ref "IC64") (pin "10") (pinfunction "DID_10") (pintype "input"))
      (node (ref "IC64") (pin "15") (pinfunction "CLR_15") (pintype "input"))
      (node (ref "IC64") (pin "9") (pinfunction "DID_9") (pintype "input"))
      (node (ref "IC67") (pin "10") (pinfunction "DID_10") (pintype "input"))
      (node (ref "IC67") (pin "15") (pinfunction "CLR_15") (pintype "input"))
      (node (ref "IC67") (pin "9") (pinfunction "DID_9") (pintype "input"))
      (node (ref "IC7") (pin "13") (pinfunction "ENA_13") (pintype "input"))
    )
    (net (code "232") (name "SYSTEMCLOCK") (class "Default")
      (node (ref "IC10") (pin "1") (pinfunction "I_1") (pintype "input"))
      (node (ref "IC4") (pin "10") (pinfunction "I1_10") (pintype "input"))
      (node (ref "JP1") (pin "3") (pinfunction "3_3") (pintype "passive"))
    )
    (net (code "233") (name "SYSTEMRESET") (class "Default")
      (node (ref "IC10") (pin "3") (pinfunction "I_3") (pintype "input"))
      (node (ref "IC26") (pin "4") (pinfunction "I0_4") (pintype "input"))
      (node (ref "IC3") (pin "13") (pinfunction "I1_13") (pintype "input"))
      (node (ref "IC3") (pin "4") (pinfunction "I0_4") (pintype "input"))
      (node (ref "IC3") (pin "9") (pinfunction "I0_9") (pintype "input"))
      (node (ref "IC40") (pin "1") (pinfunction "I0_1") (pintype "input"))
      (node (ref "IC40") (pin "4") (pinfunction "I0_4") (pintype "input"))
      (node (ref "IC45") (pin "4") (pinfunction "I0_4") (pintype "input"))
      (node (ref "IC55") (pin "2") (pinfunction "I1_2") (pintype "input"))
      (node (ref "IC62") (pin "1") (pinfunction "I0_1") (pintype "input"))
      (node (ref "IC8") (pin "4") (pinfunction "I0_4") (pintype "input"))
      (node (ref "JP1") (pin "2") (pinfunction "2_2") (pintype "passive"))
      (node (ref "V1") (pin "14") (pinfunction "CLR_14") (pintype "input"))
      (node (ref "V2") (pin "14") (pinfunction "CLR_14") (pintype "input"))
      (node (ref "V3") (pin "14") (pinfunction "CLR_14") (pintype "input"))
    )
    (net (code "234") (name "UNDERFLOW") (class "Default")
      (node (ref "IC18") (pin "3") (pinfunction "O_3") (pintype "output"))
      (node (ref "IC53") (pin "2") (pinfunction "I1_2") (pintype "input"))
    )
    (net (code "235") (name "VCC") (class "Default")
      (node (ref "IC11") (pin "21") (pinfunction "~{WE}_21") (pintype "input"))
      (node (ref "IC11") (pin "24") (pinfunction "VCC_24") (pintype "power_in"))
      (node (ref "IC12") (pin "21") (pinfunction "~{WE}_21") (pintype "input"))
      (node (ref "IC12") (pin "24") (pinfunction "VCC_24") (pintype "power_in"))
      (node (ref "IC13") (pin "21") (pinfunction "~{WE}_21") (pintype "input"))
      (node (ref "IC13") (pin "24") (pinfunction "VCC_24") (pintype "power_in"))
      (node (ref "IC14") (pin "21") (pinfunction "~{WE}_21") (pintype "input"))
      (node (ref "IC14") (pin "24") (pinfunction "VCC_24") (pintype "power_in"))
      (node (ref "IC15") (pin "21") (pinfunction "~{WE}_21") (pintype "input"))
      (node (ref "IC15") (pin "24") (pinfunction "VCC_24") (pintype "power_in"))
      (node (ref "IC2") (pin "5") (pinfunction "EN_5") (pintype "input"))
      (node (ref "IC27") (pin "5") (pinfunction "EN_5") (pintype "input"))
      (node (ref "IC32") (pin "1") (pinfunction "DIR_1") (pintype "input"))
      (node (ref "IC33") (pin "1") (pinfunction "DIR_1") (pintype "input"))
      (node (ref "IC34") (pin "5") (pinfunction "EN_5") (pintype "input"))
      (node (ref "IC35") (pin "1") (pinfunction "DIR_1") (pintype "input"))
      (node (ref "IC36") (pin "1") (pinfunction "DIR_1") (pintype "input"))
      (node (ref "IC42") (pin "6") (pinfunction "POL_6") (pintype "input"))
      (node (ref "IC43") (pin "6") (pinfunction "POL_6") (pintype "input"))
      (node (ref "IC47") (pin "1") (pinfunction "DIR_1") (pintype "input"))
      (node (ref "IC48") (pin "5") (pinfunction "EN_5") (pintype "input"))
      (node (ref "IC49") (pin "5") (pinfunction "EN_5") (pintype "input"))
      (node (ref "IC56") (pin "5") (pinfunction "EN_5") (pintype "input"))
      (node (ref "IC58") (pin "1") (pinfunction "DIR_1") (pintype "input"))
      (node (ref "IC61") (pin "5") (pinfunction "EN_5") (pintype "input"))
      (node (ref "IC9") (pin "4") (pinfunction "PRE_4") (pintype "input"))
      (node (ref "V1") (pin "4") (pinfunction "DOWN_4") (pintype "input"))
      (node (ref "V2") (pin "4") (pinfunction "DOWN_4") (pintype "input"))
      (node (ref "V3") (pin "4") (pinfunction "DOWN_4") (pintype "input"))
    )
    (net (code "236") (name "X<Y") (class "Default")
      (node (ref "IC18") (pin "11") (pinfunction "O_11") (pintype "output"))
      (node (ref "IC53") (pin "13") (pinfunction "I1_13") (pintype "input"))
    )
    (net (code "237") (name "X=Y") (class "Default")
      (node (ref "IC18") (pin "8") (pinfunction "O_8") (pintype "output"))
      (node (ref "IC53") (pin "10") (pinfunction "I1_10") (pintype "input"))
    )
    (net (code "238") (name "X>Y") (class "Default")
      (node (ref "IC19") (pin "3") (pinfunction "O_3") (pintype "output"))
      (node (ref "IC54") (pin "2") (pinfunction "I1_2") (pintype "input"))
    )
    (net (code "239") (name "XJSRLATCH") (class "Default")
      (node (ref "IC21") (pin "11") (pinfunction "O_11") (pintype "output"))
      (node (ref "IC63") (pin "7") (pinfunction "CLK_7") (pintype "input"))
    )
    (net (code "240") (name "XJSROUTPUT") (class "Default")
      (node (ref "IC21") (pin "8") (pinfunction "O_8") (pintype "output"))
      (node (ref "IC61") (pin "4") (pinfunction "S0_4") (pintype "input"))
    )
    (net (code "241") (name "XLATCH") (class "Default")
      (node (ref "IC17") (pin "11") (pinfunction "O_11") (pintype "output"))
      (node (ref "IC42") (pin "5") (pinfunction "CLK_5") (pintype "input"))
    )
    (net (code "242") (name "YJSRLATCH") (class "Default")
      (node (ref "IC21") (pin "6") (pinfunction "O_6") (pintype "output"))
      (node (ref "IC64") (pin "7") (pinfunction "CLK_7") (pintype "input"))
    )
    (net (code "243") (name "YJSROUTPUT") (class "Default")
      (node (ref "IC21") (pin "3") (pinfunction "O_3") (pintype "output"))
      (node (ref "IC61") (pin "6") (pinfunction "S1_6") (pintype "input"))
    )
    (net (code "244") (name "YLATCH") (class "Default")
      (node (ref "IC17") (pin "8") (pinfunction "O_8") (pintype "output"))
      (node (ref "IC43") (pin "5") (pinfunction "CLK_5") (pintype "input"))
    )
    (net (code "245") (name "unconnected-(IC1A-CO-Pad12)") (class "Default")
      (node (ref "IC1") (pin "12") (pinfunction "CO_12") (pintype "output"))
    )
    (net (code "246") (name "unconnected-(IC1A-Q0-Pad3)") (class "Default")
      (node (ref "IC1") (pin "3") (pinfunction "Q0_3") (pintype "output"))
    )
    (net (code "247") (name "unconnected-(IC1A-Q6-Pad5)") (class "Default")
      (node (ref "IC1") (pin "5") (pinfunction "Q6_5") (pintype "output"))
    )
    (net (code "248") (name "unconnected-(IC1A-Q8-Pad9)") (class "Default")
      (node (ref "IC1") (pin "9") (pinfunction "Q8_9") (pintype "output"))
    )
    (net (code "249") (name "unconnected-(IC1A-Q9-Pad11)") (class "Default")
      (node (ref "IC1") (pin "11") (pinfunction "Q9_11") (pintype "output"))
    )
    (net (code "250") (name "unconnected-(IC2A-Q2-Pad10)") (class "Default")
      (node (ref "IC2") (pin "10") (pinfunction "Q2_10") (pintype "output"))
    )
    (net (code "251") (name "unconnected-(IC2A-Q3-Pad1)") (class "Default")
      (node (ref "IC2") (pin "1") (pinfunction "Q3_1") (pintype "output"))
    )
    (net (code "252") (name "unconnected-(IC2A-R2-Pad11)") (class "Default")
      (node (ref "IC2") (pin "11") (pinfunction "R2_11") (pintype "input"))
    )
    (net (code "253") (name "unconnected-(IC2A-R3-Pad15)") (class "Default")
      (node (ref "IC2") (pin "15") (pinfunction "R3_15") (pintype "input"))
    )
    (net (code "254") (name "unconnected-(IC2A-S2-Pad12)") (class "Default")
      (node (ref "IC2") (pin "12") (pinfunction "S2_12") (pintype "input"))
    )
    (net (code "255") (name "unconnected-(IC2A-S3-Pad14)") (class "Default")
      (node (ref "IC2") (pin "14") (pinfunction "S3_14") (pintype "input"))
    )
    (net (code "256") (name "unconnected-(IC6A-Q6-Pad2)") (class "Default")
      (node (ref "IC6") (pin "2") (pinfunction "Q6_2") (pintype "output"))
    )
    (net (code "257") (name "unconnected-(IC6A-Q7-Pad4)") (class "Default")
      (node (ref "IC6") (pin "4") (pinfunction "Q7_4") (pintype "output"))
    )
    (net (code "258") (name "unconnected-(IC6A-Q8-Pad13)") (class "Default")
      (node (ref "IC6") (pin "13") (pinfunction "Q8_13") (pintype "output"))
    )
    (net (code "259") (name "unconnected-(IC6A-Q9-Pad12)") (class "Default")
      (node (ref "IC6") (pin "12") (pinfunction "Q9_12") (pintype "output"))
    )
    (net (code "260") (name "unconnected-(IC6A-Q10-Pad14)") (class "Default")
      (node (ref "IC6") (pin "14") (pinfunction "Q10_14") (pintype "output"))
    )
    (net (code "261") (name "unconnected-(IC6A-Q11-Pad15)") (class "Default")
      (node (ref "IC6") (pin "15") (pinfunction "Q11_15") (pintype "output"))
    )
    (net (code "262") (name "unconnected-(IC6A-Q12-Pad1)") (class "Default")
      (node (ref "IC6") (pin "1") (pinfunction "Q12_1") (pintype "output"))
    )
    (net (code "263") (name "unconnected-(IC7A-CO-Pad12)") (class "Default")
      (node (ref "IC7") (pin "12") (pinfunction "CO_12") (pintype "output"))
    )
    (net (code "264") (name "unconnected-(IC7A-Q0-Pad3)") (class "Default")
      (node (ref "IC7") (pin "3") (pinfunction "Q0_3") (pintype "output"))
    )
    (net (code "265") (name "unconnected-(IC7A-Q2-Pad4)") (class "Default")
      (node (ref "IC7") (pin "4") (pinfunction "Q2_4") (pintype "output"))
    )
    (net (code "266") (name "unconnected-(IC7A-Q4-Pad10)") (class "Default")
      (node (ref "IC7") (pin "10") (pinfunction "Q4_10") (pintype "output"))
    )
    (net (code "267") (name "unconnected-(IC7A-Q6-Pad5)") (class "Default")
      (node (ref "IC7") (pin "5") (pinfunction "Q6_5") (pintype "output"))
    )
    (net (code "268") (name "unconnected-(IC7A-Q7-Pad6)") (class "Default")
      (node (ref "IC7") (pin "6") (pinfunction "Q7_6") (pintype "output"))
    )
    (net (code "269") (name "unconnected-(IC7A-Q8-Pad9)") (class "Default")
      (node (ref "IC7") (pin "9") (pinfunction "Q8_9") (pintype "output"))
    )
    (net (code "270") (name "unconnected-(IC7A-Q9-Pad11)") (class "Default")
      (node (ref "IC7") (pin "11") (pinfunction "Q9_11") (pintype "output"))
    )
    (net (code "271") (name "unconnected-(IC9A-~{Q}-Pad6)") (class "Default")
      (node (ref "IC9") (pin "6") (pinfunction "~{Q}_6") (pintype "output"))
    )
    (net (code "272") (name "unconnected-(IC15-D5-Pad15)") (class "Default")
      (node (ref "IC15") (pin "15") (pinfunction "D5_15") (pintype "tri_state"))
    )
    (net (code "273") (name "unconnected-(IC15-D6-Pad16)") (class "Default")
      (node (ref "IC15") (pin "16") (pinfunction "D6_16") (pintype "tri_state"))
    )
    (net (code "274") (name "unconnected-(IC15-D7-Pad17)") (class "Default")
      (node (ref "IC15") (pin "17") (pinfunction "D7_17") (pintype "tri_state"))
    )
    (net (code "275") (name "unconnected-(IC25A-D3-Pad11)") (class "Default")
      (node (ref "IC25") (pin "11") (pinfunction "D3_11") (pintype "input"))
    )
    (net (code "276") (name "unconnected-(IC25A-Q3-Pad6)") (class "Default")
      (node (ref "IC25") (pin "6") (pinfunction "Q3_6") (pintype "output"))
    )
    (net (code "277") (name "unconnected-(IC27A-Q3-Pad1)") (class "Default")
      (node (ref "IC27") (pin "1") (pinfunction "Q3_1") (pintype "output"))
    )
    (net (code "278") (name "unconnected-(IC27A-R3-Pad15)") (class "Default")
      (node (ref "IC27") (pin "15") (pinfunction "R3_15") (pintype "input"))
    )
    (net (code "279") (name "unconnected-(IC27A-S3-Pad14)") (class "Default")
      (node (ref "IC27") (pin "14") (pinfunction "S3_14") (pintype "input"))
    )
    (net (code "280") (name "unconnected-(IC29A-6D-Pad14)") (class "Default")
      (node (ref "IC29") (pin "14") (pinfunction "6D_14") (pintype "input"))
    )
    (net (code "281") (name "unconnected-(IC29A-6Q-Pad15)") (class "Default")
      (node (ref "IC29") (pin "15") (pinfunction "6Q_15") (pintype "tri_state"))
    )
    (net (code "282") (name "unconnected-(IC29A-7D-Pad17)") (class "Default")
      (node (ref "IC29") (pin "17") (pinfunction "7D_17") (pintype "input"))
    )
    (net (code "283") (name "unconnected-(IC29A-7Q-Pad16)") (class "Default")
      (node (ref "IC29") (pin "16") (pinfunction "7Q_16") (pintype "tri_state"))
    )
    (net (code "284") (name "unconnected-(IC29A-8D-Pad18)") (class "Default")
      (node (ref "IC29") (pin "18") (pinfunction "8D_18") (pintype "input"))
    )
    (net (code "285") (name "unconnected-(IC29A-8Q-Pad19)") (class "Default")
      (node (ref "IC29") (pin "19") (pinfunction "8Q_19") (pintype "tri_state"))
    )
    (net (code "286") (name "unconnected-(IC33A-A4-Pad5)") (class "Default")
      (node (ref "IC33") (pin "5") (pinfunction "A4_5") (pintype "bidirectional"))
    )
    (net (code "287") (name "unconnected-(IC33A-A5-Pad6)") (class "Default")
      (node (ref "IC33") (pin "6") (pinfunction "A5_6") (pintype "bidirectional"))
    )
    (net (code "288") (name "unconnected-(IC33A-A6-Pad7)") (class "Default")
      (node (ref "IC33") (pin "7") (pinfunction "A6_7") (pintype "bidirectional"))
    )
    (net (code "289") (name "unconnected-(IC33A-A7-Pad8)") (class "Default")
      (node (ref "IC33") (pin "8") (pinfunction "A7_8") (pintype "bidirectional"))
    )
    (net (code "290") (name "unconnected-(IC33A-A8-Pad9)") (class "Default")
      (node (ref "IC33") (pin "9") (pinfunction "A8_9") (pintype "bidirectional"))
    )
    (net (code "291") (name "unconnected-(IC33A-B4-Pad15)") (class "Default")
      (node (ref "IC33") (pin "15") (pinfunction "B4_15") (pintype "bidirectional"))
    )
    (net (code "292") (name "unconnected-(IC33A-B5-Pad14)") (class "Default")
      (node (ref "IC33") (pin "14") (pinfunction "B5_14") (pintype "bidirectional"))
    )
    (net (code "293") (name "unconnected-(IC33A-B6-Pad13)") (class "Default")
      (node (ref "IC33") (pin "13") (pinfunction "B6_13") (pintype "bidirectional"))
    )
    (net (code "294") (name "unconnected-(IC33A-B7-Pad12)") (class "Default")
      (node (ref "IC33") (pin "12") (pinfunction "B7_12") (pintype "bidirectional"))
    )
    (net (code "295") (name "unconnected-(IC33A-B8-Pad11)") (class "Default")
      (node (ref "IC33") (pin "11") (pinfunction "B8_11") (pintype "bidirectional"))
    )
    (net (code "296") (name "unconnected-(IC34A-Q2-Pad10)") (class "Default")
      (node (ref "IC34") (pin "10") (pinfunction "Q2_10") (pintype "output"))
    )
    (net (code "297") (name "unconnected-(IC34A-Q3-Pad1)") (class "Default")
      (node (ref "IC34") (pin "1") (pinfunction "Q3_1") (pintype "output"))
    )
    (net (code "298") (name "unconnected-(IC34A-R2-Pad11)") (class "Default")
      (node (ref "IC34") (pin "11") (pinfunction "R2_11") (pintype "input"))
    )
    (net (code "299") (name "unconnected-(IC34A-R3-Pad15)") (class "Default")
      (node (ref "IC34") (pin "15") (pinfunction "R3_15") (pintype "input"))
    )
    (net (code "300") (name "unconnected-(IC34A-S2-Pad12)") (class "Default")
      (node (ref "IC34") (pin "12") (pinfunction "S2_12") (pintype "input"))
    )
    (net (code "301") (name "unconnected-(IC34A-S3-Pad14)") (class "Default")
      (node (ref "IC34") (pin "14") (pinfunction "S3_14") (pintype "input"))
    )
    (net (code "302") (name "unconnected-(IC36A-A4-Pad5)") (class "Default")
      (node (ref "IC36") (pin "5") (pinfunction "A4_5") (pintype "bidirectional"))
    )
    (net (code "303") (name "unconnected-(IC36A-A5-Pad6)") (class "Default")
      (node (ref "IC36") (pin "6") (pinfunction "A5_6") (pintype "bidirectional"))
    )
    (net (code "304") (name "unconnected-(IC36A-A6-Pad7)") (class "Default")
      (node (ref "IC36") (pin "7") (pinfunction "A6_7") (pintype "bidirectional"))
    )
    (net (code "305") (name "unconnected-(IC36A-A7-Pad8)") (class "Default")
      (node (ref "IC36") (pin "8") (pinfunction "A7_8") (pintype "bidirectional"))
    )
    (net (code "306") (name "unconnected-(IC36A-A8-Pad9)") (class "Default")
      (node (ref "IC36") (pin "9") (pinfunction "A8_9") (pintype "bidirectional"))
    )
    (net (code "307") (name "unconnected-(IC36A-B4-Pad15)") (class "Default")
      (node (ref "IC36") (pin "15") (pinfunction "B4_15") (pintype "bidirectional"))
    )
    (net (code "308") (name "unconnected-(IC36A-B5-Pad14)") (class "Default")
      (node (ref "IC36") (pin "14") (pinfunction "B5_14") (pintype "bidirectional"))
    )
    (net (code "309") (name "unconnected-(IC36A-B6-Pad13)") (class "Default")
      (node (ref "IC36") (pin "13") (pinfunction "B6_13") (pintype "bidirectional"))
    )
    (net (code "310") (name "unconnected-(IC36A-B7-Pad12)") (class "Default")
      (node (ref "IC36") (pin "12") (pinfunction "B7_12") (pintype "bidirectional"))
    )
    (net (code "311") (name "unconnected-(IC36A-B8-Pad11)") (class "Default")
      (node (ref "IC36") (pin "11") (pinfunction "B8_11") (pintype "bidirectional"))
    )
    (net (code "312") (name "unconnected-(IC38A-D3-Pad11)") (class "Default")
      (node (ref "IC38") (pin "11") (pinfunction "D3_11") (pintype "input"))
    )
    (net (code "313") (name "unconnected-(IC38A-Q3-Pad6)") (class "Default")
      (node (ref "IC38") (pin "6") (pinfunction "Q3_6") (pintype "output"))
    )
    (net (code "314") (name "unconnected-(IC41A-G-Pad17)") (class "Default")
      (node (ref "IC41") (pin "17") (pinfunction "G_17") (pintype "output"))
    )
    (net (code "315") (name "unconnected-(IC41A-P-Pad15)") (class "Default")
      (node (ref "IC41") (pin "15") (pinfunction "P_15") (pintype "output"))
    )
    (net (code "316") (name "unconnected-(IC42A-~{Q0}-Pad3)") (class "Default")
      (node (ref "IC42") (pin "3") (pinfunction "~{Q0}_3") (pintype "output"))
    )
    (net (code "317") (name "unconnected-(IC42A-~{Q1}-Pad9)") (class "Default")
      (node (ref "IC42") (pin "9") (pinfunction "~{Q1}_9") (pintype "output"))
    )
    (net (code "318") (name "unconnected-(IC42A-~{Q2}-Pad12)") (class "Default")
      (node (ref "IC42") (pin "12") (pinfunction "~{Q2}_12") (pintype "output"))
    )
    (net (code "319") (name "unconnected-(IC42A-~{Q3}-Pad15)") (class "Default")
      (node (ref "IC42") (pin "15") (pinfunction "~{Q3}_15") (pintype "output"))
    )
    (net (code "320") (name "unconnected-(IC43A-~{Q0}-Pad3)") (class "Default")
      (node (ref "IC43") (pin "3") (pinfunction "~{Q0}_3") (pintype "output"))
    )
    (net (code "321") (name "unconnected-(IC43A-~{Q1}-Pad9)") (class "Default")
      (node (ref "IC43") (pin "9") (pinfunction "~{Q1}_9") (pintype "output"))
    )
    (net (code "322") (name "unconnected-(IC43A-~{Q2}-Pad12)") (class "Default")
      (node (ref "IC43") (pin "12") (pinfunction "~{Q2}_12") (pintype "output"))
    )
    (net (code "323") (name "unconnected-(IC43A-~{Q3}-Pad15)") (class "Default")
      (node (ref "IC43") (pin "15") (pinfunction "~{Q3}_15") (pintype "output"))
    )
    (net (code "324") (name "unconnected-(IC47A-A6-Pad7)") (class "Default")
      (node (ref "IC47") (pin "7") (pinfunction "A6_7") (pintype "bidirectional"))
    )
    (net (code "325") (name "unconnected-(IC47A-A7-Pad8)") (class "Default")
      (node (ref "IC47") (pin "8") (pinfunction "A7_8") (pintype "bidirectional"))
    )
    (net (code "326") (name "unconnected-(IC47A-A8-Pad9)") (class "Default")
      (node (ref "IC47") (pin "9") (pinfunction "A8_9") (pintype "bidirectional"))
    )
    (net (code "327") (name "unconnected-(IC47A-B6-Pad13)") (class "Default")
      (node (ref "IC47") (pin "13") (pinfunction "B6_13") (pintype "bidirectional"))
    )
    (net (code "328") (name "unconnected-(IC47A-B7-Pad12)") (class "Default")
      (node (ref "IC47") (pin "12") (pinfunction "B7_12") (pintype "bidirectional"))
    )
    (net (code "329") (name "unconnected-(IC47A-B8-Pad11)") (class "Default")
      (node (ref "IC47") (pin "11") (pinfunction "B8_11") (pintype "bidirectional"))
    )
    (net (code "330") (name "unconnected-(IC49A-Q2-Pad10)") (class "Default")
      (node (ref "IC49") (pin "10") (pinfunction "Q2_10") (pintype "output"))
    )
    (net (code "331") (name "unconnected-(IC49A-Q3-Pad1)") (class "Default")
      (node (ref "IC49") (pin "1") (pinfunction "Q3_1") (pintype "output"))
    )
    (net (code "332") (name "unconnected-(IC49A-R2-Pad11)") (class "Default")
      (node (ref "IC49") (pin "11") (pinfunction "R2_11") (pintype "input"))
    )
    (net (code "333") (name "unconnected-(IC49A-R3-Pad15)") (class "Default")
      (node (ref "IC49") (pin "15") (pinfunction "R3_15") (pintype "input"))
    )
    (net (code "334") (name "unconnected-(IC49A-S2-Pad12)") (class "Default")
      (node (ref "IC49") (pin "12") (pinfunction "S2_12") (pintype "input"))
    )
    (net (code "335") (name "unconnected-(IC49A-S3-Pad14)") (class "Default")
      (node (ref "IC49") (pin "14") (pinfunction "S3_14") (pintype "input"))
    )
    (net (code "336") (name "unconnected-(IC56A-Q1-Pad9)") (class "Default")
      (node (ref "IC56") (pin "9") (pinfunction "Q1_9") (pintype "output"))
    )
    (net (code "337") (name "unconnected-(IC56A-Q2-Pad10)") (class "Default")
      (node (ref "IC56") (pin "10") (pinfunction "Q2_10") (pintype "output"))
    )
    (net (code "338") (name "unconnected-(IC56A-Q3-Pad1)") (class "Default")
      (node (ref "IC56") (pin "1") (pinfunction "Q3_1") (pintype "output"))
    )
    (net (code "339") (name "unconnected-(IC56A-R1-Pad7)") (class "Default")
      (node (ref "IC56") (pin "7") (pinfunction "R1_7") (pintype "input"))
    )
    (net (code "340") (name "unconnected-(IC56A-R2-Pad11)") (class "Default")
      (node (ref "IC56") (pin "11") (pinfunction "R2_11") (pintype "input"))
    )
    (net (code "341") (name "unconnected-(IC56A-R3-Pad15)") (class "Default")
      (node (ref "IC56") (pin "15") (pinfunction "R3_15") (pintype "input"))
    )
    (net (code "342") (name "unconnected-(IC56A-S1-Pad6)") (class "Default")
      (node (ref "IC56") (pin "6") (pinfunction "S1_6") (pintype "input"))
    )
    (net (code "343") (name "unconnected-(IC56A-S2-Pad12)") (class "Default")
      (node (ref "IC56") (pin "12") (pinfunction "S2_12") (pintype "input"))
    )
    (net (code "344") (name "unconnected-(IC56A-S3-Pad14)") (class "Default")
      (node (ref "IC56") (pin "14") (pinfunction "S3_14") (pintype "input"))
    )
    (net (code "345") (name "unconnected-(IC58A-A6-Pad7)") (class "Default")
      (node (ref "IC58") (pin "7") (pinfunction "A6_7") (pintype "bidirectional"))
    )
    (net (code "346") (name "unconnected-(IC58A-A7-Pad8)") (class "Default")
      (node (ref "IC58") (pin "8") (pinfunction "A7_8") (pintype "bidirectional"))
    )
    (net (code "347") (name "unconnected-(IC58A-A8-Pad9)") (class "Default")
      (node (ref "IC58") (pin "9") (pinfunction "A8_9") (pintype "bidirectional"))
    )
    (net (code "348") (name "unconnected-(IC58A-B6-Pad13)") (class "Default")
      (node (ref "IC58") (pin "13") (pinfunction "B6_13") (pintype "bidirectional"))
    )
    (net (code "349") (name "unconnected-(IC58A-B7-Pad12)") (class "Default")
      (node (ref "IC58") (pin "12") (pinfunction "B7_12") (pintype "bidirectional"))
    )
    (net (code "350") (name "unconnected-(IC58A-B8-Pad11)") (class "Default")
      (node (ref "IC58") (pin "11") (pinfunction "B8_11") (pintype "bidirectional"))
    )
    (net (code "351") (name "unconnected-(IC60A-6D-Pad14)") (class "Default")
      (node (ref "IC60") (pin "14") (pinfunction "6D_14") (pintype "input"))
    )
    (net (code "352") (name "unconnected-(IC60A-6Q-Pad15)") (class "Default")
      (node (ref "IC60") (pin "15") (pinfunction "6Q_15") (pintype "tri_state"))
    )
    (net (code "353") (name "unconnected-(IC60A-7D-Pad17)") (class "Default")
      (node (ref "IC60") (pin "17") (pinfunction "7D_17") (pintype "input"))
    )
    (net (code "354") (name "unconnected-(IC60A-7Q-Pad16)") (class "Default")
      (node (ref "IC60") (pin "16") (pinfunction "7Q_16") (pintype "tri_state"))
    )
    (net (code "355") (name "unconnected-(IC60A-8D-Pad18)") (class "Default")
      (node (ref "IC60") (pin "18") (pinfunction "8D_18") (pintype "input"))
    )
    (net (code "356") (name "unconnected-(IC60A-8Q-Pad19)") (class "Default")
      (node (ref "IC60") (pin "19") (pinfunction "8Q_19") (pintype "tri_state"))
    )
    (net (code "357") (name "unconnected-(IC65A-6D-Pad14)") (class "Default")
      (node (ref "IC65") (pin "14") (pinfunction "6D_14") (pintype "input"))
    )
    (net (code "358") (name "unconnected-(IC65A-6Q-Pad15)") (class "Default")
      (node (ref "IC65") (pin "15") (pinfunction "6Q_15") (pintype "tri_state"))
    )
    (net (code "359") (name "unconnected-(IC65A-7D-Pad17)") (class "Default")
      (node (ref "IC65") (pin "17") (pinfunction "7D_17") (pintype "input"))
    )
    (net (code "360") (name "unconnected-(IC65A-7Q-Pad16)") (class "Default")
      (node (ref "IC65") (pin "16") (pinfunction "7Q_16") (pintype "tri_state"))
    )
    (net (code "361") (name "unconnected-(IC65A-8D-Pad18)") (class "Default")
      (node (ref "IC65") (pin "18") (pinfunction "8D_18") (pintype "input"))
    )
    (net (code "362") (name "unconnected-(IC65A-8Q-Pad19)") (class "Default")
      (node (ref "IC65") (pin "19") (pinfunction "8Q_19") (pintype "tri_state"))
    )
    (net (code "363") (name "unconnected-(IC67A-D3-Pad11)") (class "Default")
      (node (ref "IC67") (pin "11") (pinfunction "D3_11") (pintype "input"))
    )
    (net (code "364") (name "unconnected-(IC67A-Q3-Pad6)") (class "Default")
      (node (ref "IC67") (pin "6") (pinfunction "Q3_6") (pintype "output"))
    )
    (net (code "365") (name "unconnected-(V1C-~{BO}-Pad13)") (class "Default")
      (node (ref "V1") (pin "13") (pinfunction "~{BO}_13") (pintype "output"))
    )
    (net (code "366") (name "unconnected-(V2C-~{BO}-Pad13)") (class "Default")
      (node (ref "V2") (pin "13") (pinfunction "~{BO}_13") (pintype "output"))
    )
    (net (code "367") (name "unconnected-(V3C-D-Pad9)") (class "Default")
      (node (ref "V3") (pin "9") (pinfunction "D_9") (pintype "input"))
    )
    (net (code "368") (name "unconnected-(V3C-QD-Pad7)") (class "Default")
      (node (ref "V3") (pin "7") (pinfunction "QD_7") (pintype "output"))
    )
    (net (code "369") (name "unconnected-(V3C-~{BO}-Pad13)") (class "Default")
      (node (ref "V3") (pin "13") (pinfunction "~{BO}_13") (pintype "output"))
    )
    (net (code "370") (name "unconnected-(V3C-~{CO}-Pad12)") (class "Default")
      (node (ref "V3") (pin "12") (pinfunction "~{CO}_12") (pintype "output"))
    )
  )
)
